# DDR4_SDRAM.net
KiCad netlist of a schematic drawn in Altium Designer
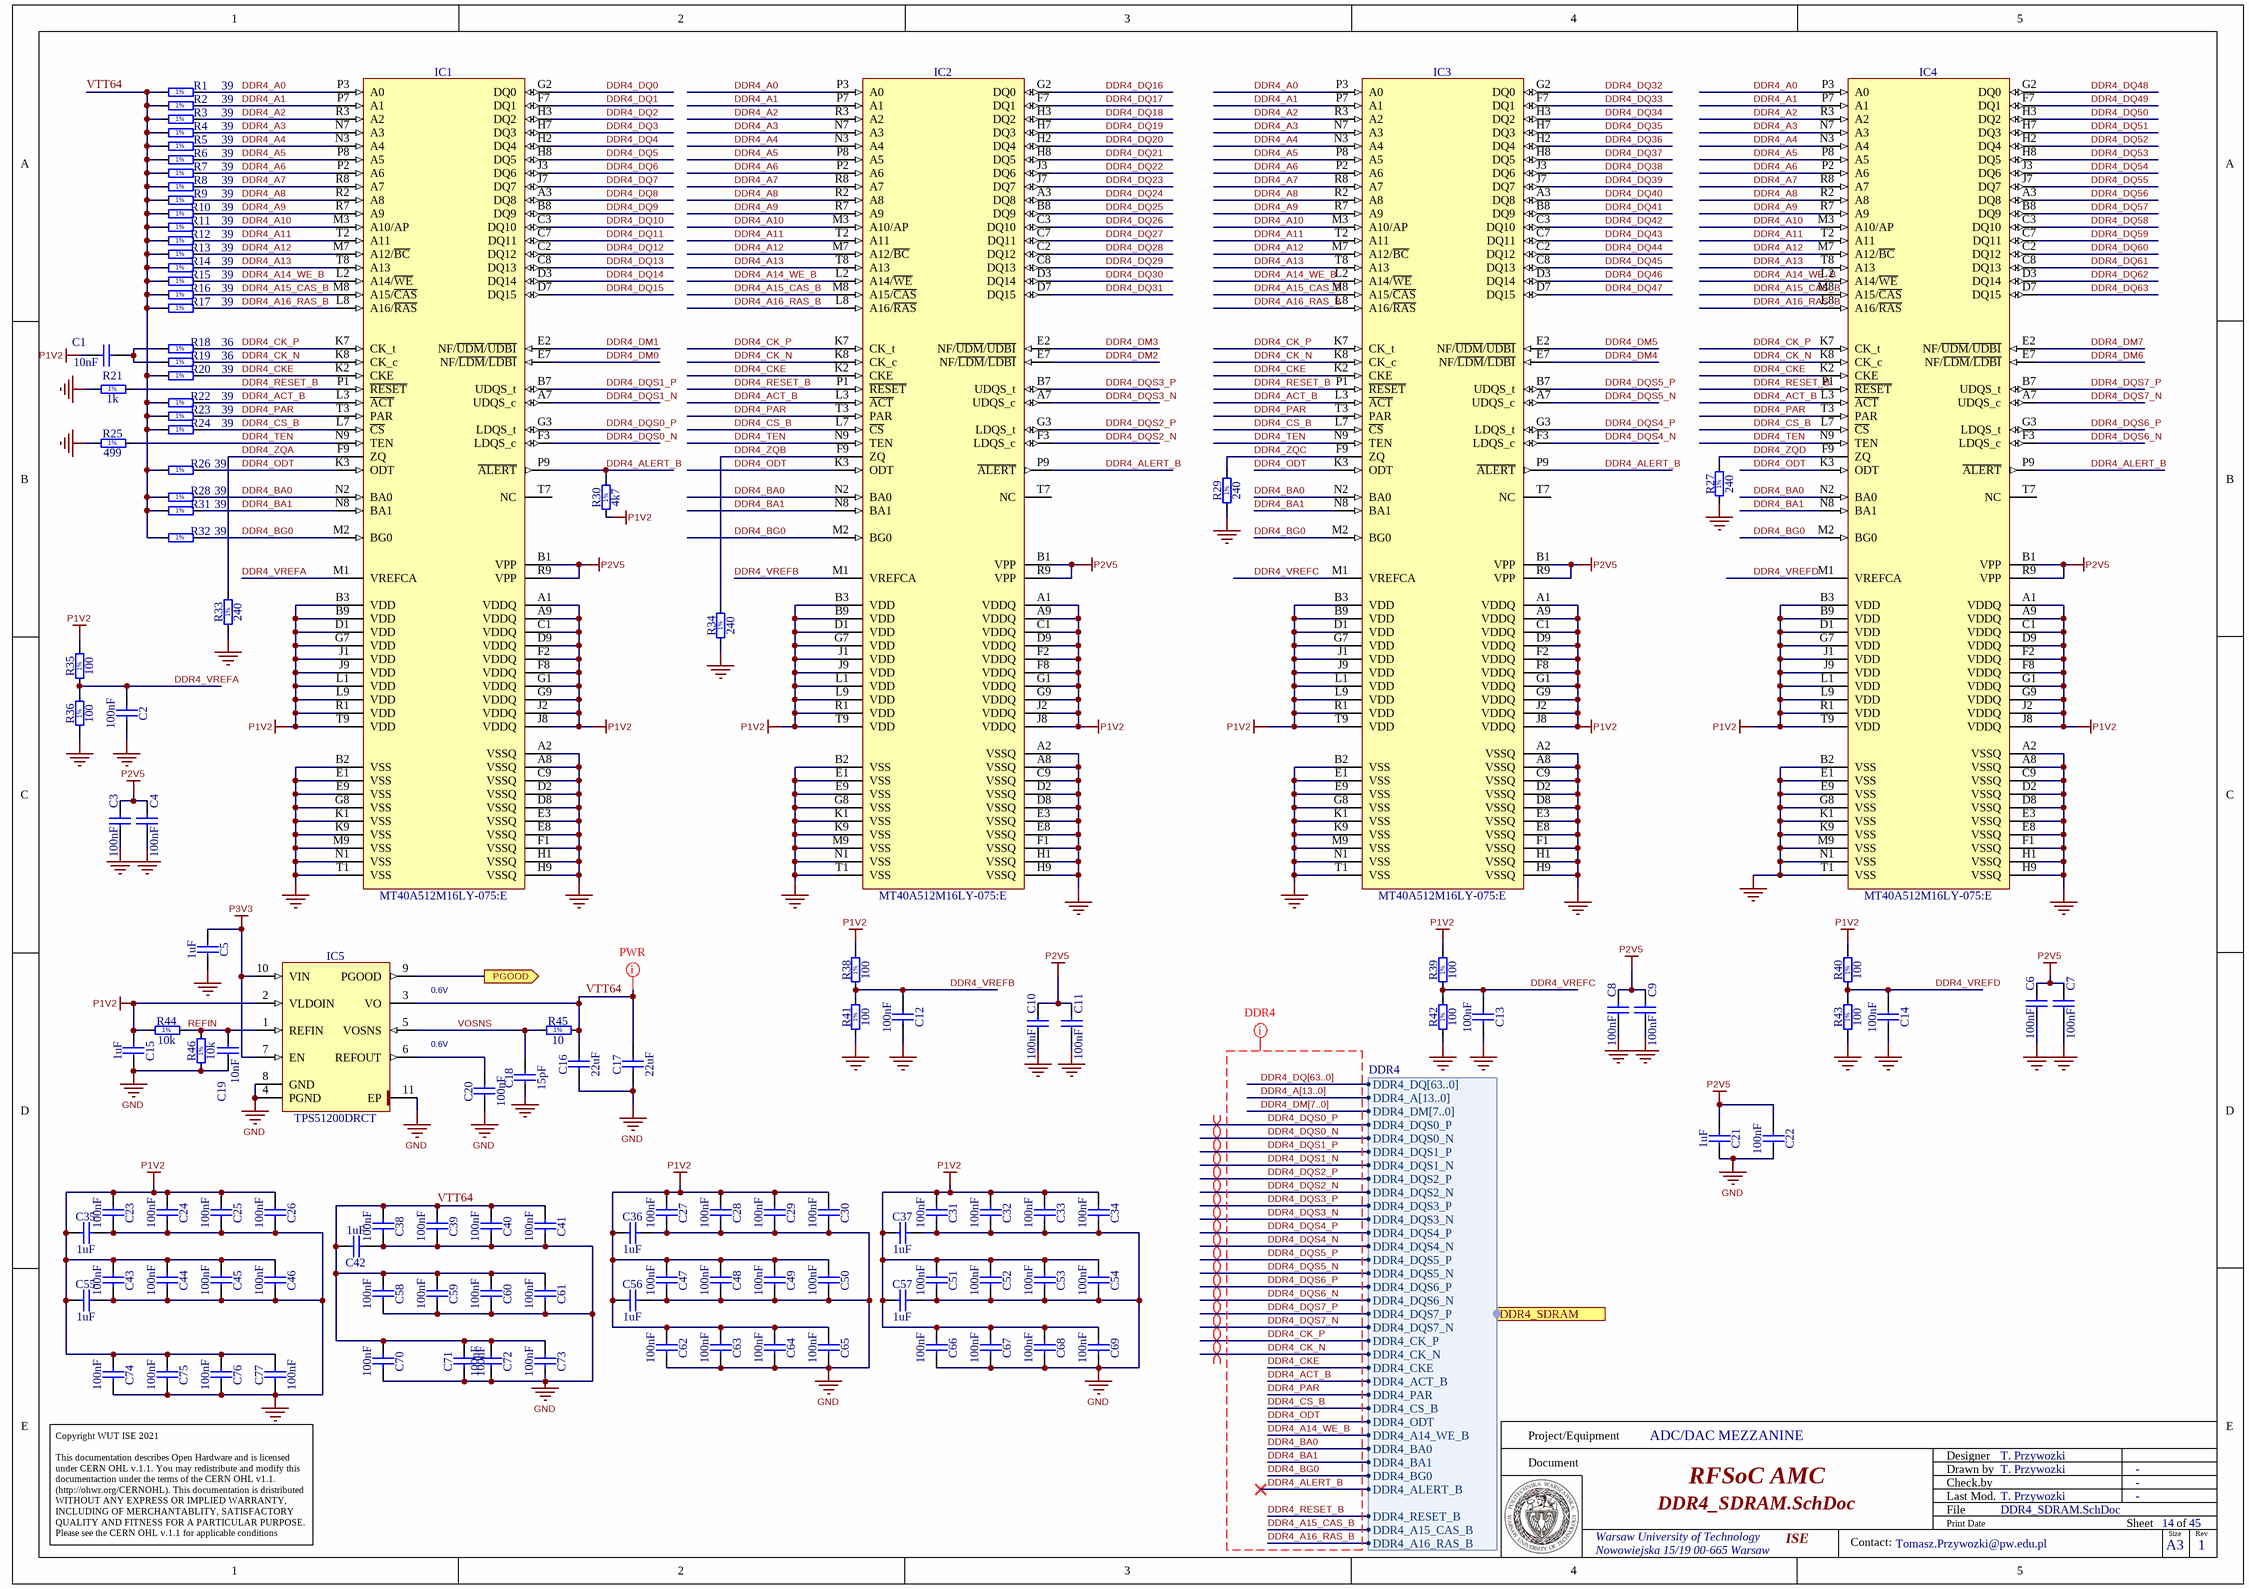
[diagram p0: DDR4_SDRAM.SchDoc]

(export (version "E")
  (design (tool "Eeschema 10.0.6"))
  (components
    (comp (ref "C1")
      (value "10nF")
      (footprint "CAPC0603X33N")
      (description "Non-polarised capacitor")
      (fields
        (field (name "PART NUMBER") "CC0201_10NF_10V_10%_X5R")
        (field (name "VOLTAGE") "10V")
        (field (name "AUTHOR") "CERN DEM JLC")
      )
      (libsource (lib "Capacitors") (part "Capacitor - non polarized"))
    )
    (comp (ref "C2")
      (value "100nF")
      (footprint "CAPC0603X33N")
      (description "Non-polarised capacitor")
      (fields
        (field (name "MANUFACTURER PART NUMBER") "CC0201_100NF_6.3V_10%_X5R")
        (field (name "MANUFACTURER") "GENERIC")
        (field (name "AUTHOR") "CERN DEM JLC")
      )
      (libsource (lib "Capacitors") (part "Capacitor - non polarized"))
    )
    (comp (ref "C3")
      (value "100nF")
      (footprint "CAPC0603X33N")
      (description "Non-polarised capacitor")
      (fields
        (field (name "MANUFACTURER PART NUMBER") "CC0201_100NF_6.3V_10%_X5R")
        (field (name "MANUFACTURER") "GENERIC")
        (field (name "AUTHOR") "CERN DEM JLC")
      )
      (libsource (lib "Capacitors") (part "Capacitor - non polarized"))
    )
    (comp (ref "C4")
      (value "100nF")
      (footprint "CAPC0603X33N")
      (description "Non-polarised capacitor")
      (fields
        (field (name "MANUFACTURER PART NUMBER") "CC0201_100NF_6.3V_10%_X5R")
        (field (name "MANUFACTURER") "GENERIC")
        (field (name "AUTHOR") "CERN DEM JLC")
      )
      (libsource (lib "Capacitors") (part "Capacitor - non polarized"))
    )
    (comp (ref "C5")
      (value "1uF")
      (footprint "CAPC1005X55N")
      (description "Non-polarised capacitor")
      (fields
        (field (name "MANUFACTURER PART NUMBER") "CC0402_1UF_16V_10%_X5R")
        (field (name "MANUFACTURER") "GENERIC")
        (field (name "AUTHOR") "CERN DEM JLC")
      )
      (libsource (lib "Capacitors") (part "Capacitor - non polarized"))
    )
    (comp (ref "C6")
      (value "100nF")
      (footprint "CAPC0603X33N")
      (description "Non-polarised capacitor")
      (fields
        (field (name "MANUFACTURER PART NUMBER") "CC0201_100NF_6.3V_10%_X5R")
        (field (name "MANUFACTURER") "GENERIC")
        (field (name "AUTHOR") "CERN DEM JLC")
      )
      (libsource (lib "Capacitors") (part "Capacitor - non polarized"))
    )
    (comp (ref "C7")
      (value "100nF")
      (footprint "CAPC0603X33N")
      (description "Non-polarised capacitor")
      (fields
        (field (name "MANUFACTURER PART NUMBER") "CC0201_100NF_6.3V_10%_X5R")
        (field (name "MANUFACTURER") "GENERIC")
        (field (name "AUTHOR") "CERN DEM JLC")
      )
      (libsource (lib "Capacitors") (part "Capacitor - non polarized"))
    )
    (comp (ref "C8")
      (value "100nF")
      (footprint "CAPC0603X33N")
      (description "Non-polarised capacitor")
      (fields
        (field (name "MANUFACTURER PART NUMBER") "CC0201_100NF_6.3V_10%_X5R")
        (field (name "MANUFACTURER") "GENERIC")
        (field (name "AUTHOR") "CERN DEM JLC")
      )
      (libsource (lib "Capacitors") (part "Capacitor - non polarized"))
    )
    (comp (ref "C9")
      (value "100nF")
      (footprint "CAPC0603X33N")
      (description "Non-polarised capacitor")
      (fields
        (field (name "MANUFACTURER PART NUMBER") "CC0201_100NF_6.3V_10%_X5R")
        (field (name "MANUFACTURER") "GENERIC")
        (field (name "AUTHOR") "CERN DEM JLC")
      )
      (libsource (lib "Capacitors") (part "Capacitor - non polarized"))
    )
    (comp (ref "C10")
      (value "100nF")
      (footprint "CAPC0603X33N")
      (description "Non-polarised capacitor")
      (fields
        (field (name "MANUFACTURER PART NUMBER") "CC0201_100NF_6.3V_10%_X5R")
        (field (name "MANUFACTURER") "GENERIC")
        (field (name "AUTHOR") "CERN DEM JLC")
      )
      (libsource (lib "Capacitors") (part "Capacitor - non polarized"))
    )
    (comp (ref "C11")
      (value "100nF")
      (footprint "CAPC0603X33N")
      (description "Non-polarised capacitor")
      (fields
        (field (name "MANUFACTURER PART NUMBER") "CC0201_100NF_6.3V_10%_X5R")
        (field (name "MANUFACTURER") "GENERIC")
        (field (name "AUTHOR") "CERN DEM JLC")
      )
      (libsource (lib "Capacitors") (part "Capacitor - non polarized"))
    )
    (comp (ref "C12")
      (value "100nF")
      (footprint "CAPC0603X33N")
      (description "Non-polarised capacitor")
      (fields
        (field (name "MANUFACTURER PART NUMBER") "CC0201_100NF_6.3V_10%_X5R")
        (field (name "MANUFACTURER") "GENERIC")
        (field (name "AUTHOR") "CERN DEM JLC")
      )
      (libsource (lib "Capacitors") (part "Capacitor - non polarized"))
    )
    (comp (ref "C13")
      (value "100nF")
      (footprint "CAPC0603X33N")
      (description "Non-polarised capacitor")
      (fields
        (field (name "MANUFACTURER PART NUMBER") "CC0201_100NF_6.3V_10%_X5R")
        (field (name "MANUFACTURER") "GENERIC")
        (field (name "AUTHOR") "CERN DEM JLC")
      )
      (libsource (lib "Capacitors") (part "Capacitor - non polarized"))
    )
    (comp (ref "C14")
      (value "100nF")
      (footprint "CAPC0603X33N")
      (description "Non-polarised capacitor")
      (fields
        (field (name "MANUFACTURER PART NUMBER") "CC0201_100NF_6.3V_10%_X5R")
        (field (name "MANUFACTURER") "GENERIC")
        (field (name "AUTHOR") "CERN DEM JLC")
      )
      (libsource (lib "Capacitors") (part "Capacitor - non polarized"))
    )
    (comp (ref "C15")
      (value "1uF")
      (footprint "CAPC1005X55N")
      (description "Non-polarised capacitor")
      (fields
        (field (name "MANUFACTURER PART NUMBER") "CC0402_1UF_16V_10%_X5R")
        (field (name "MANUFACTURER") "GENERIC")
        (field (name "AUTHOR") "CERN DEM JLC")
      )
      (libsource (lib "Capacitors") (part "Capacitor - non polarized"))
    )
    (comp (ref "C16")
      (value "22uF")
      (footprint "CAPC2012X135N")
      (description "Non-polarised capacitor")
      (fields
        (field (name "MANUFACTURER PART NUMBER") "CC0805_22UF_10V_+80%-20%_Y5V")
        (field (name "MANUFACTURER") "GENERIC")
        (field (name "AUTHOR") "CERN DEM JLC")
      )
      (libsource (lib "Capacitors") (part "Capacitor - non polarized"))
    )
    (comp (ref "C17")
      (value "22uF")
      (footprint "CAPC2012X135N")
      (description "Non-polarised capacitor")
      (fields
        (field (name "MANUFACTURER PART NUMBER") "CC0805_22UF_10V_+80%-20%_Y5V")
        (field (name "MANUFACTURER") "GENERIC")
        (field (name "AUTHOR") "CERN DEM JLC")
      )
      (libsource (lib "Capacitors") (part "Capacitor - non polarized"))
    )
    (comp (ref "C18")
      (value "15pF")
      (footprint "CAPC1005X55N")
      (description "Non-polarised capacitor")
      (fields
        (field (name "MANUFACTURER PART NUMBER") "CC0402_15PF_50V_5%_C0G")
        (field (name "MANUFACTURER") "GENERIC")
        (field (name "AUTHOR") "CERN DEM JLC")
      )
      (libsource (lib "Capacitors") (part "Capacitor - non polarized"))
    )
    (comp (ref "C19")
      (value "10nF")
      (footprint "CAPC1005X55N")
      (description "Non-polarised capacitor")
      (fields
        (field (name "MANUFACTURER PART NUMBER") "CC0402_10NF_25V_10%_X7R")
        (field (name "MANUFACTURER") "GENERIC")
        (field (name "AUTHOR") "CERN DEM JLC")
      )
      (libsource (lib "Capacitors") (part "Capacitor - non polarized"))
    )
    (comp (ref "C20")
      (value "100nF")
      (footprint "CAPC0603X33N")
      (description "Non-polarised capacitor")
      (fields
        (field (name "MANUFACTURER PART NUMBER") "CC0201_100NF_6.3V_10%_X5R")
        (field (name "MANUFACTURER") "GENERIC")
        (field (name "AUTHOR") "CERN DEM JLC")
      )
      (libsource (lib "Capacitors") (part "Capacitor - non polarized"))
    )
    (comp (ref "C21")
      (value "1uF")
      (footprint "CAPC1005X55N")
      (description "Non-polarised capacitor")
      (fields
        (field (name "MANUFACTURER PART NUMBER") "CC0402_1UF_16V_10%_X5R")
        (field (name "MANUFACTURER") "GENERIC")
        (field (name "AUTHOR") "CERN DEM JLC")
      )
      (libsource (lib "Capacitors") (part "Capacitor - non polarized"))
    )
    (comp (ref "C22")
      (value "100nF")
      (footprint "CAPC0603X33N")
      (description "Non-polarised capacitor")
      (fields
        (field (name "MANUFACTURER PART NUMBER") "CC0201_100NF_6.3V_10%_X5R")
        (field (name "MANUFACTURER") "GENERIC")
        (field (name "AUTHOR") "CERN DEM JLC")
      )
      (libsource (lib "Capacitors") (part "Capacitor - non polarized"))
    )
    (comp (ref "C23")
      (value "100nF")
      (footprint "CAPC0603X33N")
      (description "Non-polarised capacitor")
      (fields
        (field (name "MANUFACTURER PART NUMBER") "CC0201_100NF_6.3V_10%_X5R")
        (field (name "MANUFACTURER") "GENERIC")
        (field (name "AUTHOR") "CERN DEM JLC")
      )
      (libsource (lib "Capacitors") (part "Capacitor - non polarized"))
    )
    (comp (ref "C24")
      (value "100nF")
      (footprint "CAPC0603X33N")
      (description "Non-polarised capacitor")
      (fields
        (field (name "MANUFACTURER PART NUMBER") "CC0201_100NF_6.3V_10%_X5R")
        (field (name "MANUFACTURER") "GENERIC")
        (field (name "AUTHOR") "CERN DEM JLC")
      )
      (libsource (lib "Capacitors") (part "Capacitor - non polarized"))
    )
    (comp (ref "C25")
      (value "100nF")
      (footprint "CAPC0603X33N")
      (description "Non-polarised capacitor")
      (fields
        (field (name "MANUFACTURER PART NUMBER") "CC0201_100NF_6.3V_10%_X5R")
        (field (name "MANUFACTURER") "GENERIC")
        (field (name "AUTHOR") "CERN DEM JLC")
      )
      (libsource (lib "Capacitors") (part "Capacitor - non polarized"))
    )
    (comp (ref "C26")
      (value "100nF")
      (footprint "CAPC0603X33N")
      (description "Non-polarised capacitor")
      (fields
        (field (name "MANUFACTURER PART NUMBER") "CC0201_100NF_6.3V_10%_X5R")
        (field (name "MANUFACTURER") "GENERIC")
        (field (name "AUTHOR") "CERN DEM JLC")
      )
      (libsource (lib "Capacitors") (part "Capacitor - non polarized"))
    )
    (comp (ref "C27")
      (value "100nF")
      (footprint "CAPC0603X33N")
      (description "Non-polarised capacitor")
      (fields
        (field (name "MANUFACTURER PART NUMBER") "CC0201_100NF_6.3V_10%_X5R")
        (field (name "MANUFACTURER") "GENERIC")
        (field (name "AUTHOR") "CERN DEM JLC")
      )
      (libsource (lib "Capacitors") (part "Capacitor - non polarized"))
    )
    (comp (ref "C28")
      (value "100nF")
      (footprint "CAPC0603X33N")
      (description "Non-polarised capacitor")
      (fields
        (field (name "MANUFACTURER PART NUMBER") "CC0201_100NF_6.3V_10%_X5R")
        (field (name "MANUFACTURER") "GENERIC")
        (field (name "AUTHOR") "CERN DEM JLC")
      )
      (libsource (lib "Capacitors") (part "Capacitor - non polarized"))
    )
    (comp (ref "C29")
      (value "100nF")
      (footprint "CAPC0603X33N")
      (description "Non-polarised capacitor")
      (fields
        (field (name "MANUFACTURER PART NUMBER") "CC0201_100NF_6.3V_10%_X5R")
        (field (name "MANUFACTURER") "GENERIC")
        (field (name "AUTHOR") "CERN DEM JLC")
      )
      (libsource (lib "Capacitors") (part "Capacitor - non polarized"))
    )
    (comp (ref "C30")
      (value "100nF")
      (footprint "CAPC0603X33N")
      (description "Non-polarised capacitor")
      (fields
        (field (name "MANUFACTURER PART NUMBER") "CC0201_100NF_6.3V_10%_X5R")
        (field (name "MANUFACTURER") "GENERIC")
        (field (name "AUTHOR") "CERN DEM JLC")
      )
      (libsource (lib "Capacitors") (part "Capacitor - non polarized"))
    )
    (comp (ref "C31")
      (value "100nF")
      (footprint "CAPC0603X33N")
      (description "Non-polarised capacitor")
      (fields
        (field (name "MANUFACTURER PART NUMBER") "CC0201_100NF_6.3V_10%_X5R")
        (field (name "MANUFACTURER") "GENERIC")
        (field (name "AUTHOR") "CERN DEM JLC")
      )
      (libsource (lib "Capacitors") (part "Capacitor - non polarized"))
    )
    (comp (ref "C32")
      (value "100nF")
      (footprint "CAPC0603X33N")
      (description "Non-polarised capacitor")
      (fields
        (field (name "MANUFACTURER PART NUMBER") "CC0201_100NF_6.3V_10%_X5R")
        (field (name "MANUFACTURER") "GENERIC")
        (field (name "AUTHOR") "CERN DEM JLC")
      )
      (libsource (lib "Capacitors") (part "Capacitor - non polarized"))
    )
    (comp (ref "C33")
      (value "100nF")
      (footprint "CAPC0603X33N")
      (description "Non-polarised capacitor")
      (fields
        (field (name "MANUFACTURER PART NUMBER") "CC0201_100NF_6.3V_10%_X5R")
        (field (name "MANUFACTURER") "GENERIC")
        (field (name "AUTHOR") "CERN DEM JLC")
      )
      (libsource (lib "Capacitors") (part "Capacitor - non polarized"))
    )
    (comp (ref "C34")
      (value "100nF")
      (footprint "CAPC0603X33N")
      (description "Non-polarised capacitor")
      (fields
        (field (name "MANUFACTURER PART NUMBER") "CC0201_100NF_6.3V_10%_X5R")
        (field (name "MANUFACTURER") "GENERIC")
        (field (name "AUTHOR") "CERN DEM JLC")
      )
      (libsource (lib "Capacitors") (part "Capacitor - non polarized"))
    )
    (comp (ref "C35")
      (value "1uF")
      (footprint "CAPC1005X55N")
      (description "Non-polarised capacitor")
      (fields
        (field (name "MANUFACTURER PART NUMBER") "CC0402_1UF_16V_10%_X5R")
        (field (name "MANUFACTURER") "GENERIC")
        (field (name "AUTHOR") "CERN DEM JLC")
      )
      (libsource (lib "Capacitors") (part "Capacitor - non polarized"))
    )
    (comp (ref "C36")
      (value "1uF")
      (footprint "CAPC1005X55N")
      (description "Non-polarised capacitor")
      (fields
        (field (name "MANUFACTURER PART NUMBER") "CC0402_1UF_16V_10%_X5R")
        (field (name "MANUFACTURER") "GENERIC")
        (field (name "AUTHOR") "CERN DEM JLC")
      )
      (libsource (lib "Capacitors") (part "Capacitor - non polarized"))
    )
    (comp (ref "C37")
      (value "1uF")
      (footprint "CAPC1005X55N")
      (description "Non-polarised capacitor")
      (fields
        (field (name "MANUFACTURER PART NUMBER") "CC0402_1UF_16V_10%_X5R")
        (field (name "MANUFACTURER") "GENERIC")
        (field (name "AUTHOR") "CERN DEM JLC")
      )
      (libsource (lib "Capacitors") (part "Capacitor - non polarized"))
    )
    (comp (ref "C38")
      (value "100nF")
      (footprint "CAPC0603X33N")
      (description "Non-polarised capacitor")
      (fields
        (field (name "MANUFACTURER PART NUMBER") "CC0201_100NF_6.3V_10%_X5R")
        (field (name "MANUFACTURER") "GENERIC")
        (field (name "AUTHOR") "CERN DEM JLC")
      )
      (libsource (lib "Capacitors") (part "Capacitor - non polarized"))
    )
    (comp (ref "C39")
      (value "100nF")
      (footprint "CAPC0603X33N")
      (description "Non-polarised capacitor")
      (fields
        (field (name "MANUFACTURER PART NUMBER") "CC0201_100NF_6.3V_10%_X5R")
        (field (name "MANUFACTURER") "GENERIC")
        (field (name "AUTHOR") "CERN DEM JLC")
      )
      (libsource (lib "Capacitors") (part "Capacitor - non polarized"))
    )
    (comp (ref "C40")
      (value "100nF")
      (footprint "CAPC0603X33N")
      (description "Non-polarised capacitor")
      (fields
        (field (name "MANUFACTURER PART NUMBER") "CC0201_100NF_6.3V_10%_X5R")
        (field (name "MANUFACTURER") "GENERIC")
        (field (name "AUTHOR") "CERN DEM JLC")
      )
      (libsource (lib "Capacitors") (part "Capacitor - non polarized"))
    )
    (comp (ref "C41")
      (value "100nF")
      (footprint "CAPC0603X33N")
      (description "Non-polarised capacitor")
      (fields
        (field (name "MANUFACTURER PART NUMBER") "CC0201_100NF_6.3V_10%_X5R")
        (field (name "MANUFACTURER") "GENERIC")
        (field (name "AUTHOR") "CERN DEM JLC")
      )
      (libsource (lib "Capacitors") (part "Capacitor - non polarized"))
    )
    (comp (ref "C42")
      (value "1uF")
      (footprint "CAPC1005X55N")
      (description "Non-polarised capacitor")
      (fields
        (field (name "MANUFACTURER PART NUMBER") "CC0402_1UF_16V_10%_X5R")
        (field (name "MANUFACTURER") "GENERIC")
        (field (name "AUTHOR") "CERN DEM JLC")
      )
      (libsource (lib "Capacitors") (part "Capacitor - non polarized"))
    )
    (comp (ref "C43")
      (value "100nF")
      (footprint "CAPC0603X33N")
      (description "Non-polarised capacitor")
      (fields
        (field (name "MANUFACTURER PART NUMBER") "CC0201_100NF_6.3V_10%_X5R")
        (field (name "MANUFACTURER") "GENERIC")
        (field (name "AUTHOR") "CERN DEM JLC")
      )
      (libsource (lib "Capacitors") (part "Capacitor - non polarized"))
    )
    (comp (ref "C44")
      (value "100nF")
      (footprint "CAPC0603X33N")
      (description "Non-polarised capacitor")
      (fields
        (field (name "MANUFACTURER PART NUMBER") "CC0201_100NF_6.3V_10%_X5R")
        (field (name "MANUFACTURER") "GENERIC")
        (field (name "AUTHOR") "CERN DEM JLC")
      )
      (libsource (lib "Capacitors") (part "Capacitor - non polarized"))
    )
    (comp (ref "C45")
      (value "100nF")
      (footprint "CAPC0603X33N")
      (description "Non-polarised capacitor")
      (fields
        (field (name "MANUFACTURER PART NUMBER") "CC0201_100NF_6.3V_10%_X5R")
        (field (name "MANUFACTURER") "GENERIC")
        (field (name "AUTHOR") "CERN DEM JLC")
      )
      (libsource (lib "Capacitors") (part "Capacitor - non polarized"))
    )
    (comp (ref "C46")
      (value "100nF")
      (footprint "CAPC0603X33N")
      (description "Non-polarised capacitor")
      (fields
        (field (name "MANUFACTURER PART NUMBER") "CC0201_100NF_6.3V_10%_X5R")
        (field (name "MANUFACTURER") "GENERIC")
        (field (name "AUTHOR") "CERN DEM JLC")
      )
      (libsource (lib "Capacitors") (part "Capacitor - non polarized"))
    )
    (comp (ref "C47")
      (value "100nF")
      (footprint "CAPC0603X33N")
      (description "Non-polarised capacitor")
      (fields
        (field (name "MANUFACTURER PART NUMBER") "CC0201_100NF_6.3V_10%_X5R")
        (field (name "MANUFACTURER") "GENERIC")
        (field (name "AUTHOR") "CERN DEM JLC")
      )
      (libsource (lib "Capacitors") (part "Capacitor - non polarized"))
    )
    (comp (ref "C48")
      (value "100nF")
      (footprint "CAPC0603X33N")
      (description "Non-polarised capacitor")
      (fields
        (field (name "MANUFACTURER PART NUMBER") "CC0201_100NF_6.3V_10%_X5R")
        (field (name "MANUFACTURER") "GENERIC")
        (field (name "AUTHOR") "CERN DEM JLC")
      )
      (libsource (lib "Capacitors") (part "Capacitor - non polarized"))
    )
    (comp (ref "C49")
      (value "100nF")
      (footprint "CAPC0603X33N")
      (description "Non-polarised capacitor")
      (fields
        (field (name "MANUFACTURER PART NUMBER") "CC0201_100NF_6.3V_10%_X5R")
        (field (name "MANUFACTURER") "GENERIC")
        (field (name "AUTHOR") "CERN DEM JLC")
      )
      (libsource (lib "Capacitors") (part "Capacitor - non polarized"))
    )
    (comp (ref "C50")
      (value "100nF")
      (footprint "CAPC0603X33N")
      (description "Non-polarised capacitor")
      (fields
        (field (name "MANUFACTURER PART NUMBER") "CC0201_100NF_6.3V_10%_X5R")
        (field (name "MANUFACTURER") "GENERIC")
        (field (name "AUTHOR") "CERN DEM JLC")
      )
      (libsource (lib "Capacitors") (part "Capacitor - non polarized"))
    )
    (comp (ref "C51")
      (value "100nF")
      (footprint "CAPC0603X33N")
      (description "Non-polarised capacitor")
      (fields
        (field (name "MANUFACTURER PART NUMBER") "CC0201_100NF_6.3V_10%_X5R")
        (field (name "MANUFACTURER") "GENERIC")
        (field (name "AUTHOR") "CERN DEM JLC")
      )
      (libsource (lib "Capacitors") (part "Capacitor - non polarized"))
    )
    (comp (ref "C52")
      (value "100nF")
      (footprint "CAPC0603X33N")
      (description "Non-polarised capacitor")
      (fields
        (field (name "MANUFACTURER PART NUMBER") "CC0201_100NF_6.3V_10%_X5R")
        (field (name "MANUFACTURER") "GENERIC")
        (field (name "AUTHOR") "CERN DEM JLC")
      )
      (libsource (lib "Capacitors") (part "Capacitor - non polarized"))
    )
    (comp (ref "C53")
      (value "100nF")
      (footprint "CAPC0603X33N")
      (description "Non-polarised capacitor")
      (fields
        (field (name "MANUFACTURER PART NUMBER") "CC0201_100NF_6.3V_10%_X5R")
        (field (name "MANUFACTURER") "GENERIC")
        (field (name "AUTHOR") "CERN DEM JLC")
      )
      (libsource (lib "Capacitors") (part "Capacitor - non polarized"))
    )
    (comp (ref "C54")
      (value "100nF")
      (footprint "CAPC0603X33N")
      (description "Non-polarised capacitor")
      (fields
        (field (name "MANUFACTURER PART NUMBER") "CC0201_100NF_6.3V_10%_X5R")
        (field (name "MANUFACTURER") "GENERIC")
        (field (name "AUTHOR") "CERN DEM JLC")
      )
      (libsource (lib "Capacitors") (part "Capacitor - non polarized"))
    )
    (comp (ref "C55")
      (value "1uF")
      (footprint "CAPC1005X55N")
      (description "Non-polarised capacitor")
      (fields
        (field (name "MANUFACTURER PART NUMBER") "CC0402_1UF_16V_10%_X5R")
        (field (name "MANUFACTURER") "GENERIC")
        (field (name "AUTHOR") "CERN DEM JLC")
      )
      (libsource (lib "Capacitors") (part "Capacitor - non polarized"))
    )
    (comp (ref "C56")
      (value "1uF")
      (footprint "CAPC1005X55N")
      (description "Non-polarised capacitor")
      (fields
        (field (name "MANUFACTURER PART NUMBER") "CC0402_1UF_16V_10%_X5R")
        (field (name "MANUFACTURER") "GENERIC")
        (field (name "AUTHOR") "CERN DEM JLC")
      )
      (libsource (lib "Capacitors") (part "Capacitor - non polarized"))
    )
    (comp (ref "C57")
      (value "1uF")
      (footprint "CAPC1005X55N")
      (description "Non-polarised capacitor")
      (fields
        (field (name "MANUFACTURER PART NUMBER") "CC0402_1UF_16V_10%_X5R")
        (field (name "MANUFACTURER") "GENERIC")
        (field (name "AUTHOR") "CERN DEM JLC")
      )
      (libsource (lib "Capacitors") (part "Capacitor - non polarized"))
    )
    (comp (ref "C58")
      (value "100nF")
      (footprint "CAPC0603X33N")
      (description "Non-polarised capacitor")
      (fields
        (field (name "MANUFACTURER PART NUMBER") "CC0201_100NF_6.3V_10%_X5R")
        (field (name "MANUFACTURER") "GENERIC")
        (field (name "AUTHOR") "CERN DEM JLC")
      )
      (libsource (lib "Capacitors") (part "Capacitor - non polarized"))
    )
    (comp (ref "C59")
      (value "100nF")
      (footprint "CAPC0603X33N")
      (description "Non-polarised capacitor")
      (fields
        (field (name "MANUFACTURER PART NUMBER") "CC0201_100NF_6.3V_10%_X5R")
        (field (name "MANUFACTURER") "GENERIC")
        (field (name "AUTHOR") "CERN DEM JLC")
      )
      (libsource (lib "Capacitors") (part "Capacitor - non polarized"))
    )
    (comp (ref "C60")
      (value "100nF")
      (footprint "CAPC0603X33N")
      (description "Non-polarised capacitor")
      (fields
        (field (name "MANUFACTURER PART NUMBER") "CC0201_100NF_6.3V_10%_X5R")
        (field (name "MANUFACTURER") "GENERIC")
        (field (name "AUTHOR") "CERN DEM JLC")
      )
      (libsource (lib "Capacitors") (part "Capacitor - non polarized"))
    )
    (comp (ref "C61")
      (value "100nF")
      (footprint "CAPC0603X33N")
      (description "Non-polarised capacitor")
      (fields
        (field (name "MANUFACTURER PART NUMBER") "CC0201_100NF_6.3V_10%_X5R")
        (field (name "MANUFACTURER") "GENERIC")
        (field (name "AUTHOR") "CERN DEM JLC")
      )
      (libsource (lib "Capacitors") (part "Capacitor - non polarized"))
    )
    (comp (ref "C62")
      (value "100nF")
      (footprint "CAPC0603X33N")
      (description "Non-polarised capacitor")
      (fields
        (field (name "MANUFACTURER PART NUMBER") "CC0201_100NF_6.3V_10%_X5R")
        (field (name "MANUFACTURER") "GENERIC")
        (field (name "AUTHOR") "CERN DEM JLC")
      )
      (libsource (lib "Capacitors") (part "Capacitor - non polarized"))
    )
    (comp (ref "C63")
      (value "100nF")
      (footprint "CAPC0603X33N")
      (description "Non-polarised capacitor")
      (fields
        (field (name "MANUFACTURER PART NUMBER") "CC0201_100NF_6.3V_10%_X5R")
        (field (name "MANUFACTURER") "GENERIC")
        (field (name "AUTHOR") "CERN DEM JLC")
      )
      (libsource (lib "Capacitors") (part "Capacitor - non polarized"))
    )
    (comp (ref "C64")
      (value "100nF")
      (footprint "CAPC0603X33N")
      (description "Non-polarised capacitor")
      (fields
        (field (name "MANUFACTURER PART NUMBER") "CC0201_100NF_6.3V_10%_X5R")
        (field (name "MANUFACTURER") "GENERIC")
        (field (name "AUTHOR") "CERN DEM JLC")
      )
      (libsource (lib "Capacitors") (part "Capacitor - non polarized"))
    )
    (comp (ref "C65")
      (value "100nF")
      (footprint "CAPC0603X33N")
      (description "Non-polarised capacitor")
      (fields
        (field (name "MANUFACTURER PART NUMBER") "CC0201_100NF_6.3V_10%_X5R")
        (field (name "MANUFACTURER") "GENERIC")
        (field (name "AUTHOR") "CERN DEM JLC")
      )
      (libsource (lib "Capacitors") (part "Capacitor - non polarized"))
    )
    (comp (ref "C66")
      (value "100nF")
      (footprint "CAPC0603X33N")
      (description "Non-polarised capacitor")
      (fields
        (field (name "MANUFACTURER PART NUMBER") "CC0201_100NF_6.3V_10%_X5R")
        (field (name "MANUFACTURER") "GENERIC")
        (field (name "AUTHOR") "CERN DEM JLC")
      )
      (libsource (lib "Capacitors") (part "Capacitor - non polarized"))
    )
    (comp (ref "C67")
      (value "100nF")
      (footprint "CAPC0603X33N")
      (description "Non-polarised capacitor")
      (fields
        (field (name "MANUFACTURER PART NUMBER") "CC0201_100NF_6.3V_10%_X5R")
        (field (name "MANUFACTURER") "GENERIC")
        (field (name "AUTHOR") "CERN DEM JLC")
      )
      (libsource (lib "Capacitors") (part "Capacitor - non polarized"))
    )
    (comp (ref "C68")
      (value "100nF")
      (footprint "CAPC0603X33N")
      (description "Non-polarised capacitor")
      (fields
        (field (name "MANUFACTURER PART NUMBER") "CC0201_100NF_6.3V_10%_X5R")
        (field (name "MANUFACTURER") "GENERIC")
        (field (name "AUTHOR") "CERN DEM JLC")
      )
      (libsource (lib "Capacitors") (part "Capacitor - non polarized"))
    )
    (comp (ref "C69")
      (value "100nF")
      (footprint "CAPC0603X33N")
      (description "Non-polarised capacitor")
      (fields
        (field (name "MANUFACTURER PART NUMBER") "CC0201_100NF_6.3V_10%_X5R")
        (field (name "MANUFACTURER") "GENERIC")
        (field (name "AUTHOR") "CERN DEM JLC")
      )
      (libsource (lib "Capacitors") (part "Capacitor - non polarized"))
    )
    (comp (ref "C70")
      (value "100nF")
      (footprint "CAPC0603X33N")
      (description "Non-polarised capacitor")
      (fields
        (field (name "MANUFACTURER PART NUMBER") "CC0201_100NF_6.3V_10%_X5R")
        (field (name "MANUFACTURER") "GENERIC")
        (field (name "AUTHOR") "CERN DEM JLC")
      )
      (libsource (lib "Capacitors") (part "Capacitor - non polarized"))
    )
    (comp (ref "C71")
      (value "100nF")
      (footprint "CAPC0603X33N")
      (description "Non-polarised capacitor")
      (fields
        (field (name "MANUFACTURER PART NUMBER") "CC0201_100NF_6.3V_10%_X5R")
        (field (name "MANUFACTURER") "GENERIC")
        (field (name "AUTHOR") "CERN DEM JLC")
      )
      (libsource (lib "Capacitors") (part "Capacitor - non polarized"))
    )
    (comp (ref "C72")
      (value "100nF")
      (footprint "CAPC0603X33N")
      (description "Non-polarised capacitor")
      (fields
        (field (name "MANUFACTURER PART NUMBER") "CC0201_100NF_6.3V_10%_X5R")
        (field (name "MANUFACTURER") "GENERIC")
        (field (name "AUTHOR") "CERN DEM JLC")
      )
      (libsource (lib "Capacitors") (part "Capacitor - non polarized"))
    )
    (comp (ref "C73")
      (value "100nF")
      (footprint "CAPC0603X33N")
      (description "Non-polarised capacitor")
      (fields
        (field (name "MANUFACTURER PART NUMBER") "CC0201_100NF_6.3V_10%_X5R")
        (field (name "MANUFACTURER") "GENERIC")
        (field (name "AUTHOR") "CERN DEM JLC")
      )
      (libsource (lib "Capacitors") (part "Capacitor - non polarized"))
    )
    (comp (ref "C74")
      (value "100nF")
      (footprint "CAPC0603X33N")
      (description "Non-polarised capacitor")
      (fields
        (field (name "MANUFACTURER PART NUMBER") "CC0201_100NF_6.3V_10%_X5R")
        (field (name "MANUFACTURER") "GENERIC")
        (field (name "AUTHOR") "CERN DEM JLC")
      )
      (libsource (lib "Capacitors") (part "Capacitor - non polarized"))
    )
    (comp (ref "C75")
      (value "100nF")
      (footprint "CAPC0603X33N")
      (description "Non-polarised capacitor")
      (fields
        (field (name "MANUFACTURER PART NUMBER") "CC0201_100NF_6.3V_10%_X5R")
        (field (name "MANUFACTURER") "GENERIC")
        (field (name "AUTHOR") "CERN DEM JLC")
      )
      (libsource (lib "Capacitors") (part "Capacitor - non polarized"))
    )
    (comp (ref "C76")
      (value "100nF")
      (footprint "CAPC0603X33N")
      (description "Non-polarised capacitor")
      (fields
        (field (name "MANUFACTURER PART NUMBER") "CC0201_100NF_6.3V_10%_X5R")
        (field (name "MANUFACTURER") "GENERIC")
        (field (name "AUTHOR") "CERN DEM JLC")
      )
      (libsource (lib "Capacitors") (part "Capacitor - non polarized"))
    )
    (comp (ref "C77")
      (value "100nF")
      (footprint "CAPC0603X33N")
      (description "Non-polarised capacitor")
      (fields
        (field (name "MANUFACTURER PART NUMBER") "CC0201_100NF_6.3V_10%_X5R")
        (field (name "MANUFACTURER") "GENERIC")
        (field (name "AUTHOR") "CERN DEM JLC")
      )
      (libsource (lib "Capacitors") (part "Capacitor - non polarized"))
    )
    (comp (ref "IC1")
      (value "MT40A512M16LY-075:E")
      (footprint "BGA96C80P9X16_750X1350X120")
      (description "+1.2V, 8Gb (512 Meg x 16 x 8 Banks) DDR4 SDRAM")
      (fields (field (name "MANUFACTURER") "MICRON TECHNOLOGY") (field (name "AUTHOR") "CERN DEM WB"))
      (libsource (lib "ICs And Semiconductors") (part "MT40A512M16LY"))
    )
    (comp (ref "IC2")
      (value "MT40A512M16LY-075:E")
      (footprint "BGA96C80P9X16_750X1350X120")
      (description "+1.2V, 8Gb (512 Meg x 16 x 8 Banks) DDR4 SDRAM")
      (fields (field (name "MANUFACTURER") "MICRON TECHNOLOGY") (field (name "AUTHOR") "CERN DEM WB"))
      (libsource (lib "ICs And Semiconductors") (part "MT40A512M16LY"))
    )
    (comp (ref "IC3")
      (value "MT40A512M16LY-075:E")
      (footprint "BGA96C80P9X16_750X1350X120")
      (description "+1.2V, 8Gb (512 Meg x 16 x 8 Banks) DDR4 SDRAM")
      (fields (field (name "MANUFACTURER") "MICRON TECHNOLOGY") (field (name "AUTHOR") "CERN DEM WB"))
      (libsource (lib "ICs And Semiconductors") (part "MT40A512M16LY"))
    )
    (comp (ref "IC4")
      (value "MT40A512M16LY-075:E")
      (footprint "BGA96C80P9X16_750X1350X120")
      (description "+1.2V, 8Gb (512 Meg x 16 x 8 Banks) DDR4 SDRAM")
      (fields (field (name "MANUFACTURER") "MICRON TECHNOLOGY") (field (name "AUTHOR") "CERN DEM WB"))
      (libsource (lib "ICs And Semiconductors") (part "MT40A512M16LY"))
    )
    (comp (ref "IC5")
      (value "TPS51200DRCT")
      (footprint "TEXAS_DRC (S-PVSON-N10)")
      (description "Sink/Source DDR Termination Regulator")
      (fields (field (name "MANUFACTURER") "TEXAS INSTRUMENTS") (field (name "AUTHOR") "CERN DEM JLC"))
      (libsource (lib "ICs And Semiconductors") (part "TPS51200DRC"))
    )
    (comp (ref "R1")
      (value "39")
      (footprint "RESC1005X40N")
      (description "Resistor - 1%")
      (fields
        (field (name "MANUFACTURER PART NUMBER") "R0402_39R_1%_0.0625W_100PPM")
        (field (name "MANUFACTURER") "GENERIC")
        (field (name "AUTHOR") "CERN DEM JLC")
      )
      (libsource (lib "Resistors") (part "Resistor - 1%"))
    )
    (comp (ref "R2")
      (value "39")
      (footprint "RESC1005X40N")
      (description "Resistor - 1%")
      (fields
        (field (name "MANUFACTURER PART NUMBER") "R0402_39R_1%_0.0625W_100PPM")
        (field (name "MANUFACTURER") "GENERIC")
        (field (name "AUTHOR") "CERN DEM JLC")
      )
      (libsource (lib "Resistors") (part "Resistor - 1%"))
    )
    (comp (ref "R3")
      (value "39")
      (footprint "RESC1005X40N")
      (description "Resistor - 1%")
      (fields
        (field (name "MANUFACTURER PART NUMBER") "R0402_39R_1%_0.0625W_100PPM")
        (field (name "MANUFACTURER") "GENERIC")
        (field (name "AUTHOR") "CERN DEM JLC")
      )
      (libsource (lib "Resistors") (part "Resistor - 1%"))
    )
    (comp (ref "R4")
      (value "39")
      (footprint "RESC1005X40N")
      (description "Resistor - 1%")
      (fields
        (field (name "MANUFACTURER PART NUMBER") "R0402_39R_1%_0.0625W_100PPM")
        (field (name "MANUFACTURER") "GENERIC")
        (field (name "AUTHOR") "CERN DEM JLC")
      )
      (libsource (lib "Resistors") (part "Resistor - 1%"))
    )
    (comp (ref "R5")
      (value "39")
      (footprint "RESC1005X40N")
      (description "Resistor - 1%")
      (fields
        (field (name "MANUFACTURER PART NUMBER") "R0402_39R_1%_0.0625W_100PPM")
        (field (name "MANUFACTURER") "GENERIC")
        (field (name "AUTHOR") "CERN DEM JLC")
      )
      (libsource (lib "Resistors") (part "Resistor - 1%"))
    )
    (comp (ref "R6")
      (value "39")
      (footprint "RESC1005X40N")
      (description "Resistor - 1%")
      (fields
        (field (name "MANUFACTURER PART NUMBER") "R0402_39R_1%_0.0625W_100PPM")
        (field (name "MANUFACTURER") "GENERIC")
        (field (name "AUTHOR") "CERN DEM JLC")
      )
      (libsource (lib "Resistors") (part "Resistor - 1%"))
    )
    (comp (ref "R7")
      (value "39")
      (footprint "RESC1005X40N")
      (description "Resistor - 1%")
      (fields
        (field (name "MANUFACTURER PART NUMBER") "R0402_39R_1%_0.0625W_100PPM")
        (field (name "MANUFACTURER") "GENERIC")
        (field (name "AUTHOR") "CERN DEM JLC")
      )
      (libsource (lib "Resistors") (part "Resistor - 1%"))
    )
    (comp (ref "R8")
      (value "39")
      (footprint "RESC1005X40N")
      (description "Resistor - 1%")
      (fields
        (field (name "MANUFACTURER PART NUMBER") "R0402_39R_1%_0.0625W_100PPM")
        (field (name "MANUFACTURER") "GENERIC")
        (field (name "AUTHOR") "CERN DEM JLC")
      )
      (libsource (lib "Resistors") (part "Resistor - 1%"))
    )
    (comp (ref "R9")
      (value "39")
      (footprint "RESC1005X40N")
      (description "Resistor - 1%")
      (fields
        (field (name "MANUFACTURER PART NUMBER") "R0402_39R_1%_0.0625W_100PPM")
        (field (name "MANUFACTURER") "GENERIC")
        (field (name "AUTHOR") "CERN DEM JLC")
      )
      (libsource (lib "Resistors") (part "Resistor - 1%"))
    )
    (comp (ref "R10")
      (value "39")
      (footprint "RESC1005X40N")
      (description "Resistor - 1%")
      (fields
        (field (name "MANUFACTURER PART NUMBER") "R0402_39R_1%_0.0625W_100PPM")
        (field (name "MANUFACTURER") "GENERIC")
        (field (name "AUTHOR") "CERN DEM JLC")
      )
      (libsource (lib "Resistors") (part "Resistor - 1%"))
    )
    (comp (ref "R11")
      (value "39")
      (footprint "RESC1005X40N")
      (description "Resistor - 1%")
      (fields
        (field (name "MANUFACTURER PART NUMBER") "R0402_39R_1%_0.0625W_100PPM")
        (field (name "MANUFACTURER") "GENERIC")
        (field (name "AUTHOR") "CERN DEM JLC")
      )
      (libsource (lib "Resistors") (part "Resistor - 1%"))
    )
    (comp (ref "R12")
      (value "39")
      (footprint "RESC1005X40N")
      (description "Resistor - 1%")
      (fields
        (field (name "MANUFACTURER PART NUMBER") "R0402_39R_1%_0.0625W_100PPM")
        (field (name "MANUFACTURER") "GENERIC")
        (field (name "AUTHOR") "CERN DEM JLC")
      )
      (libsource (lib "Resistors") (part "Resistor - 1%"))
    )
    (comp (ref "R13")
      (value "39")
      (footprint "RESC1005X40N")
      (description "Resistor - 1%")
      (fields
        (field (name "MANUFACTURER PART NUMBER") "R0402_39R_1%_0.0625W_100PPM")
        (field (name "MANUFACTURER") "GENERIC")
        (field (name "AUTHOR") "CERN DEM JLC")
      )
      (libsource (lib "Resistors") (part "Resistor - 1%"))
    )
    (comp (ref "R14")
      (value "39")
      (footprint "RESC1005X40N")
      (description "Resistor - 1%")
      (fields
        (field (name "MANUFACTURER PART NUMBER") "R0402_39R_1%_0.0625W_100PPM")
        (field (name "MANUFACTURER") "GENERIC")
        (field (name "AUTHOR") "CERN DEM JLC")
      )
      (libsource (lib "Resistors") (part "Resistor - 1%"))
    )
    (comp (ref "R15")
      (value "39")
      (footprint "RESC1005X40N")
      (description "Resistor - 1%")
      (fields
        (field (name "MANUFACTURER PART NUMBER") "R0402_39R_1%_0.0625W_100PPM")
        (field (name "MANUFACTURER") "GENERIC")
        (field (name "AUTHOR") "CERN DEM JLC")
      )
      (libsource (lib "Resistors") (part "Resistor - 1%"))
    )
    (comp (ref "R16")
      (value "39")
      (footprint "RESC1005X40N")
      (description "Resistor - 1%")
      (fields
        (field (name "MANUFACTURER PART NUMBER") "R0402_39R_1%_0.0625W_100PPM")
        (field (name "MANUFACTURER") "GENERIC")
        (field (name "AUTHOR") "CERN DEM JLC")
      )
      (libsource (lib "Resistors") (part "Resistor - 1%"))
    )
    (comp (ref "R17")
      (value "39")
      (footprint "RESC1005X40N")
      (description "Resistor - 1%")
      (fields
        (field (name "MANUFACTURER PART NUMBER") "R0402_39R_1%_0.0625W_100PPM")
        (field (name "MANUFACTURER") "GENERIC")
        (field (name "AUTHOR") "CERN DEM JLC")
      )
      (libsource (lib "Resistors") (part "Resistor - 1%"))
    )
    (comp (ref "R18")
      (value "36")
      (footprint "RESC1005X40N")
      (description "Resistor - 1%")
      (fields
        (field (name "MANUFACTURER PART NUMBER") "R0402_36R_1%_0.0625W_100PPM")
        (field (name "MANUFACTURER") "GENERIC")
        (field (name "AUTHOR") "CERN DEM JLC")
      )
      (libsource (lib "Resistors") (part "Resistor - 1%"))
    )
    (comp (ref "R19")
      (value "36")
      (footprint "RESC1005X40N")
      (description "Resistor - 1%")
      (fields
        (field (name "MANUFACTURER PART NUMBER") "R0402_36R_1%_0.0625W_100PPM")
        (field (name "MANUFACTURER") "GENERIC")
        (field (name "AUTHOR") "CERN DEM JLC")
      )
      (libsource (lib "Resistors") (part "Resistor - 1%"))
    )
    (comp (ref "R20")
      (value "39")
      (footprint "RESC1005X40N")
      (description "Resistor - 1%")
      (fields
        (field (name "MANUFACTURER PART NUMBER") "R0402_39R_1%_0.0625W_100PPM")
        (field (name "MANUFACTURER") "GENERIC")
        (field (name "AUTHOR") "CERN DEM JLC")
      )
      (libsource (lib "Resistors") (part "Resistor - 1%"))
    )
    (comp (ref "R21")
      (value "1k")
      (footprint "RESC1005X40N")
      (description "Resistor - 1%")
      (fields
        (field (name "MANUFACTURER PART NUMBER") "R0402_1K_1%_0.0625W_100PPM")
        (field (name "MANUFACTURER") "GENERIC")
        (field (name "AUTHOR") "CERN DEM JLC")
      )
      (libsource (lib "Resistors") (part "Resistor - 1%"))
    )
    (comp (ref "R22")
      (value "39")
      (footprint "RESC1005X40N")
      (description "Resistor - 1%")
      (fields
        (field (name "MANUFACTURER PART NUMBER") "R0402_39R_1%_0.0625W_100PPM")
        (field (name "MANUFACTURER") "GENERIC")
        (field (name "AUTHOR") "CERN DEM JLC")
      )
      (libsource (lib "Resistors") (part "Resistor - 1%"))
    )
    (comp (ref "R23")
      (value "39")
      (footprint "RESC1005X40N")
      (description "Resistor - 1%")
      (fields
        (field (name "MANUFACTURER PART NUMBER") "R0402_39R_1%_0.0625W_100PPM")
        (field (name "MANUFACTURER") "GENERIC")
        (field (name "AUTHOR") "CERN DEM JLC")
      )
      (libsource (lib "Resistors") (part "Resistor - 1%"))
    )
    (comp (ref "R24")
      (value "39")
      (footprint "RESC1005X40N")
      (description "Resistor - 1%")
      (fields
        (field (name "MANUFACTURER PART NUMBER") "R0402_39R_1%_0.0625W_100PPM")
        (field (name "MANUFACTURER") "GENERIC")
        (field (name "AUTHOR") "CERN DEM JLC")
      )
      (libsource (lib "Resistors") (part "Resistor - 1%"))
    )
    (comp (ref "R25")
      (value "499")
      (footprint "RESC1005X40N")
      (description "Resistor - 1%")
      (fields
        (field (name "PART NUMBER") "R0402_499R_1%_0.0625W_100PPM")
        (field (name "POWER") "0.0625W")
        (field (name "AUTHOR") "CERN DEM BC")
      )
      (libsource (lib "Resistors") (part "Resistor - 1%"))
    )
    (comp (ref "R26")
      (value "39")
      (footprint "RESC1005X40N")
      (description "Resistor - 1%")
      (fields
        (field (name "MANUFACTURER PART NUMBER") "R0402_39R_1%_0.0625W_100PPM")
        (field (name "MANUFACTURER") "GENERIC")
        (field (name "AUTHOR") "CERN DEM JLC")
      )
      (libsource (lib "Resistors") (part "Resistor - 1%"))
    )
    (comp (ref "R27")
      (value "240")
      (footprint "RESC1005X40N")
      (description "Resistor - 1%")
      (fields
        (field (name "MANUFACTURER PART NUMBER") "R0402_240R_1%_0.0625W_100PPM")
        (field (name "MANUFACTURER") "GENERIC")
        (field (name "AUTHOR") "CERN DEM JLC")
      )
      (libsource (lib "Resistors") (part "Resistor - 1%"))
    )
    (comp (ref "R28")
      (value "39")
      (footprint "RESC1005X40N")
      (description "Resistor - 1%")
      (fields
        (field (name "MANUFACTURER PART NUMBER") "R0402_39R_1%_0.0625W_100PPM")
        (field (name "MANUFACTURER") "GENERIC")
        (field (name "AUTHOR") "CERN DEM JLC")
      )
      (libsource (lib "Resistors") (part "Resistor - 1%"))
    )
    (comp (ref "R29")
      (value "240")
      (footprint "RESC1005X40N")
      (description "Resistor - 1%")
      (fields
        (field (name "MANUFACTURER PART NUMBER") "R0402_240R_1%_0.0625W_100PPM")
        (field (name "MANUFACTURER") "GENERIC")
        (field (name "AUTHOR") "CERN DEM JLC")
      )
      (libsource (lib "Resistors") (part "Resistor - 1%"))
    )
    (comp (ref "R30")
      (value "4k7")
      (footprint "RESC1005X40N")
      (description "Resistor - 1%")
      (fields
        (field (name "MANUFACTURER PART NUMBER") "R0402_4K7_1%_0.0625W_100PPM")
        (field (name "MANUFACTURER") "GENERIC")
        (field (name "AUTHOR") "CERN DEM JLC")
      )
      (libsource (lib "Resistors") (part "Resistor - 1%"))
    )
    (comp (ref "R31")
      (value "39")
      (footprint "RESC1005X40N")
      (description "Resistor - 1%")
      (fields
        (field (name "MANUFACTURER PART NUMBER") "R0402_39R_1%_0.0625W_100PPM")
        (field (name "MANUFACTURER") "GENERIC")
        (field (name "AUTHOR") "CERN DEM JLC")
      )
      (libsource (lib "Resistors") (part "Resistor - 1%"))
    )
    (comp (ref "R32")
      (value "39")
      (footprint "RESC1005X40N")
      (description "Resistor - 1%")
      (fields
        (field (name "MANUFACTURER PART NUMBER") "R0402_39R_1%_0.0625W_100PPM")
        (field (name "MANUFACTURER") "GENERIC")
        (field (name "AUTHOR") "CERN DEM JLC")
      )
      (libsource (lib "Resistors") (part "Resistor - 1%"))
    )
    (comp (ref "R33")
      (value "240")
      (footprint "RESC1005X40N")
      (description "Resistor - 1%")
      (fields
        (field (name "MANUFACTURER PART NUMBER") "R0402_240R_1%_0.0625W_100PPM")
        (field (name "MANUFACTURER") "GENERIC")
        (field (name "AUTHOR") "CERN DEM JLC")
      )
      (libsource (lib "Resistors") (part "Resistor - 1%"))
    )
    (comp (ref "R34")
      (value "240")
      (footprint "RESC1005X40N")
      (description "Resistor - 1%")
      (fields
        (field (name "MANUFACTURER PART NUMBER") "R0402_240R_1%_0.0625W_100PPM")
        (field (name "MANUFACTURER") "GENERIC")
        (field (name "AUTHOR") "CERN DEM JLC")
      )
      (libsource (lib "Resistors") (part "Resistor - 1%"))
    )
    (comp (ref "R35")
      (value "100")
      (footprint "RESC1005X40N")
      (description "Resistor - 1%")
      (fields
        (field (name "MANUFACTURER PART NUMBER") "R0402_100R_1%_0.0625W_100PPM")
        (field (name "MANUFACTURER") "GENERIC")
        (field (name "AUTHOR") "CERN DEM JLC")
      )
      (libsource (lib "Resistors") (part "Resistor - 1%"))
    )
    (comp (ref "R36")
      (value "100")
      (footprint "RESC1005X40N")
      (description "Resistor - 1%")
      (fields
        (field (name "MANUFACTURER PART NUMBER") "R0402_100R_1%_0.0625W_100PPM")
        (field (name "MANUFACTURER") "GENERIC")
        (field (name "AUTHOR") "CERN DEM JLC")
      )
      (libsource (lib "Resistors") (part "Resistor - 1%"))
    )
    (comp (ref "R38")
      (value "100")
      (footprint "RESC1005X40N")
      (description "Resistor - 1%")
      (fields
        (field (name "MANUFACTURER PART NUMBER") "R0402_100R_1%_0.0625W_100PPM")
        (field (name "MANUFACTURER") "GENERIC")
        (field (name "AUTHOR") "CERN DEM JLC")
      )
      (libsource (lib "Resistors") (part "Resistor - 1%"))
    )
    (comp (ref "R39")
      (value "100")
      (footprint "RESC1005X40N")
      (description "Resistor - 1%")
      (fields
        (field (name "MANUFACTURER PART NUMBER") "R0402_100R_1%_0.0625W_100PPM")
        (field (name "MANUFACTURER") "GENERIC")
        (field (name "AUTHOR") "CERN DEM JLC")
      )
      (libsource (lib "Resistors") (part "Resistor - 1%"))
    )
    (comp (ref "R40")
      (value "100")
      (footprint "RESC1005X40N")
      (description "Resistor - 1%")
      (fields
        (field (name "MANUFACTURER PART NUMBER") "R0402_100R_1%_0.0625W_100PPM")
        (field (name "MANUFACTURER") "GENERIC")
        (field (name "AUTHOR") "CERN DEM JLC")
      )
      (libsource (lib "Resistors") (part "Resistor - 1%"))
    )
    (comp (ref "R41")
      (value "100")
      (footprint "RESC1005X40N")
      (description "Resistor - 1%")
      (fields
        (field (name "MANUFACTURER PART NUMBER") "R0402_100R_1%_0.0625W_100PPM")
        (field (name "MANUFACTURER") "GENERIC")
        (field (name "AUTHOR") "CERN DEM JLC")
      )
      (libsource (lib "Resistors") (part "Resistor - 1%"))
    )
    (comp (ref "R42")
      (value "100")
      (footprint "RESC1005X40N")
      (description "Resistor - 1%")
      (fields
        (field (name "MANUFACTURER PART NUMBER") "R0402_100R_1%_0.0625W_100PPM")
        (field (name "MANUFACTURER") "GENERIC")
        (field (name "AUTHOR") "CERN DEM JLC")
      )
      (libsource (lib "Resistors") (part "Resistor - 1%"))
    )
    (comp (ref "R43")
      (value "100")
      (footprint "RESC1005X40N")
      (description "Resistor - 1%")
      (fields
        (field (name "MANUFACTURER PART NUMBER") "R0402_100R_1%_0.0625W_100PPM")
        (field (name "MANUFACTURER") "GENERIC")
        (field (name "AUTHOR") "CERN DEM JLC")
      )
      (libsource (lib "Resistors") (part "Resistor - 1%"))
    )
    (comp (ref "R44")
      (value "10k")
      (footprint "RESC1005X40N")
      (description "Resistor - 1%")
      (fields
        (field (name "MANUFACTURER PART NUMBER") "R0402_10K_1%_0.0625W_100PPM")
        (field (name "MANUFACTURER") "GENERIC")
        (field (name "AUTHOR") "CERN DEM JLC")
      )
      (libsource (lib "Resistors") (part "Resistor - 1%"))
    )
    (comp (ref "R45")
      (value "10")
      (footprint "RESC1005X40N")
      (description "Resistor - 1%")
      (fields
        (field (name "MANUFACTURER PART NUMBER") "R0402_10R_1%_0.0625W_200PPM")
        (field (name "MANUFACTURER") "GENERIC")
        (field (name "AUTHOR") "CERN DEM JLC")
      )
      (libsource (lib "Resistors") (part "Resistor - 1%"))
    )
    (comp (ref "R46")
      (value "10k")
      (footprint "RESC1005X40N")
      (description "Resistor - 1%")
      (fields
        (field (name "MANUFACTURER PART NUMBER") "R0402_10K_1%_0.0625W_100PPM")
        (field (name "MANUFACTURER") "GENERIC")
        (field (name "AUTHOR") "CERN DEM JLC")
      )
      (libsource (lib "Resistors") (part "Resistor - 1%"))
    )
  )
  (nets
    (net (code "2") (name "/DDR4_A0") (class "Default")
      (node (ref "IC1") (pin "P3") (pinfunction "A0_P3") (pintype "input"))
      (node (ref "IC2") (pin "P3") (pinfunction "A0_P3") (pintype "input"))
      (node (ref "IC3") (pin "P3") (pinfunction "A0_P3") (pintype "input"))
      (node (ref "IC4") (pin "P3") (pinfunction "A0_P3") (pintype "input"))
      (node (ref "R1") (pin "2") (pinfunction "2_2") (pintype "passive"))
    )
    (net (code "3") (name "/DDR4_A1") (class "Default")
      (node (ref "IC1") (pin "P7") (pinfunction "A1_P7") (pintype "input"))
      (node (ref "IC2") (pin "P7") (pinfunction "A1_P7") (pintype "input"))
      (node (ref "IC3") (pin "P7") (pinfunction "A1_P7") (pintype "input"))
      (node (ref "IC4") (pin "P7") (pinfunction "A1_P7") (pintype "input"))
      (node (ref "R2") (pin "2") (pinfunction "2_2") (pintype "passive"))
    )
    (net (code "4") (name "/DDR4_A2") (class "Default")
      (node (ref "IC1") (pin "R3") (pinfunction "A2_R3") (pintype "input"))
      (node (ref "IC2") (pin "R3") (pinfunction "A2_R3") (pintype "input"))
      (node (ref "IC3") (pin "R3") (pinfunction "A2_R3") (pintype "input"))
      (node (ref "IC4") (pin "R3") (pinfunction "A2_R3") (pintype "input"))
      (node (ref "R3") (pin "2") (pinfunction "2_2") (pintype "passive"))
    )
    (net (code "5") (name "/DDR4_A3") (class "Default")
      (node (ref "IC1") (pin "N7") (pinfunction "A3_N7") (pintype "input"))
      (node (ref "IC2") (pin "N7") (pinfunction "A3_N7") (pintype "input"))
      (node (ref "IC3") (pin "N7") (pinfunction "A3_N7") (pintype "input"))
      (node (ref "IC4") (pin "N7") (pinfunction "A3_N7") (pintype "input"))
      (node (ref "R4") (pin "2") (pinfunction "2_2") (pintype "passive"))
    )
    (net (code "6") (name "/DDR4_A4") (class "Default")
      (node (ref "IC1") (pin "N3") (pinfunction "A4_N3") (pintype "input"))
      (node (ref "IC2") (pin "N3") (pinfunction "A4_N3") (pintype "input"))
      (node (ref "IC3") (pin "N3") (pinfunction "A4_N3") (pintype "input"))
      (node (ref "IC4") (pin "N3") (pinfunction "A4_N3") (pintype "input"))
      (node (ref "R5") (pin "2") (pinfunction "2_2") (pintype "passive"))
    )
    (net (code "7") (name "/DDR4_A5") (class "Default")
      (node (ref "IC1") (pin "P8") (pinfunction "A5_P8") (pintype "input"))
      (node (ref "IC2") (pin "P8") (pinfunction "A5_P8") (pintype "input"))
      (node (ref "IC3") (pin "P8") (pinfunction "A5_P8") (pintype "input"))
      (node (ref "IC4") (pin "P8") (pinfunction "A5_P8") (pintype "input"))
      (node (ref "R6") (pin "2") (pinfunction "2_2") (pintype "passive"))
    )
    (net (code "8") (name "/DDR4_A6") (class "Default")
      (node (ref "IC1") (pin "P2") (pinfunction "A6_P2") (pintype "input"))
      (node (ref "IC2") (pin "P2") (pinfunction "A6_P2") (pintype "input"))
      (node (ref "IC3") (pin "P2") (pinfunction "A6_P2") (pintype "input"))
      (node (ref "IC4") (pin "P2") (pinfunction "A6_P2") (pintype "input"))
      (node (ref "R7") (pin "2") (pinfunction "2_2") (pintype "passive"))
    )
    (net (code "9") (name "/DDR4_A7") (class "Default")
      (node (ref "IC1") (pin "R8") (pinfunction "A7_R8") (pintype "input"))
      (node (ref "IC2") (pin "R8") (pinfunction "A7_R8") (pintype "input"))
      (node (ref "IC3") (pin "R8") (pinfunction "A7_R8") (pintype "input"))
      (node (ref "IC4") (pin "R8") (pinfunction "A7_R8") (pintype "input"))
      (node (ref "R8") (pin "2") (pinfunction "2_2") (pintype "passive"))
    )
    (net (code "10") (name "/DDR4_A8") (class "Default")
      (node (ref "IC1") (pin "R2") (pinfunction "A8_R2") (pintype "input"))
      (node (ref "IC2") (pin "R2") (pinfunction "A8_R2") (pintype "input"))
      (node (ref "IC3") (pin "R2") (pinfunction "A8_R2") (pintype "input"))
      (node (ref "IC4") (pin "R2") (pinfunction "A8_R2") (pintype "input"))
      (node (ref "R9") (pin "2") (pinfunction "2_2") (pintype "passive"))
    )
    (net (code "11") (name "/DDR4_A9") (class "Default")
      (node (ref "IC1") (pin "R7") (pinfunction "A9_R7") (pintype "input"))
      (node (ref "IC2") (pin "R7") (pinfunction "A9_R7") (pintype "input"))
      (node (ref "IC3") (pin "R7") (pinfunction "A9_R7") (pintype "input"))
      (node (ref "IC4") (pin "R7") (pinfunction "A9_R7") (pintype "input"))
      (node (ref "R10") (pin "2") (pinfunction "2_2") (pintype "passive"))
    )
    (net (code "12") (name "/DDR4_A10") (class "Default")
      (node (ref "IC1") (pin "M3") (pinfunction "A10/AP_M3") (pintype "input"))
      (node (ref "IC2") (pin "M3") (pinfunction "A10/AP_M3") (pintype "input"))
      (node (ref "IC3") (pin "M3") (pinfunction "A10/AP_M3") (pintype "input"))
      (node (ref "IC4") (pin "M3") (pinfunction "A10/AP_M3") (pintype "input"))
      (node (ref "R11") (pin "2") (pinfunction "2_2") (pintype "passive"))
    )
    (net (code "13") (name "/DDR4_A11") (class "Default")
      (node (ref "IC1") (pin "T2") (pinfunction "A11_T2") (pintype "input"))
      (node (ref "IC2") (pin "T2") (pinfunction "A11_T2") (pintype "input"))
      (node (ref "IC3") (pin "T2") (pinfunction "A11_T2") (pintype "input"))
      (node (ref "IC4") (pin "T2") (pinfunction "A11_T2") (pintype "input"))
      (node (ref "R12") (pin "2") (pinfunction "2_2") (pintype "passive"))
    )
    (net (code "14") (name "/DDR4_A12") (class "Default")
      (node (ref "IC1") (pin "M7") (pinfunction "A12/~{BC}_M7") (pintype "input"))
      (node (ref "IC2") (pin "M7") (pinfunction "A12/~{BC}_M7") (pintype "input"))
      (node (ref "IC3") (pin "M7") (pinfunction "A12/~{BC}_M7") (pintype "input"))
      (node (ref "IC4") (pin "M7") (pinfunction "A12/~{BC}_M7") (pintype "input"))
      (node (ref "R13") (pin "2") (pinfunction "2_2") (pintype "passive"))
    )
    (net (code "15") (name "/DDR4_A13") (class "Default")
      (node (ref "IC1") (pin "T8") (pinfunction "A13_T8") (pintype "input"))
      (node (ref "IC2") (pin "T8") (pinfunction "A13_T8") (pintype "input"))
      (node (ref "IC3") (pin "T8") (pinfunction "A13_T8") (pintype "input"))
      (node (ref "IC4") (pin "T8") (pinfunction "A13_T8") (pintype "input"))
      (node (ref "R14") (pin "2") (pinfunction "2_2") (pintype "passive"))
    )
    (net (code "16") (name "/DDR4_A14_WE_B") (class "Default")
      (node (ref "IC1") (pin "L2") (pinfunction "A14/~{WE}_L2") (pintype "input"))
      (node (ref "IC2") (pin "L2") (pinfunction "A14/~{WE}_L2") (pintype "input"))
      (node (ref "IC3") (pin "L2") (pinfunction "A14/~{WE}_L2") (pintype "input"))
      (node (ref "IC4") (pin "L2") (pinfunction "A14/~{WE}_L2") (pintype "input"))
      (node (ref "R15") (pin "2") (pinfunction "2_2") (pintype "passive"))
    )
    (net (code "17") (name "/DDR4_A15_CAS_B") (class "Default")
      (node (ref "IC1") (pin "M8") (pinfunction "A15/~{CAS}_M8") (pintype "input"))
      (node (ref "IC2") (pin "M8") (pinfunction "A15/~{CAS}_M8") (pintype "input"))
      (node (ref "IC3") (pin "M8") (pinfunction "A15/~{CAS}_M8") (pintype "input"))
      (node (ref "IC4") (pin "M8") (pinfunction "A15/~{CAS}_M8") (pintype "input"))
      (node (ref "R16") (pin "2") (pinfunction "2_2") (pintype "passive"))
    )
    (net (code "18") (name "/DDR4_A16_RAS_B") (class "Default")
      (node (ref "IC1") (pin "L8") (pinfunction "A16/~{RAS}_L8") (pintype "input"))
      (node (ref "IC2") (pin "L8") (pinfunction "A16/~{RAS}_L8") (pintype "input"))
      (node (ref "IC3") (pin "L8") (pinfunction "A16/~{RAS}_L8") (pintype "input"))
      (node (ref "IC4") (pin "L8") (pinfunction "A16/~{RAS}_L8") (pintype "input"))
      (node (ref "R17") (pin "2") (pinfunction "2_2") (pintype "passive"))
    )
    (net (code "19") (name "/DDR4_ACT_B") (class "Default")
      (node (ref "IC1") (pin "L3") (pinfunction "~{ACT}_L3") (pintype "input"))
      (node (ref "IC2") (pin "L3") (pinfunction "~{ACT}_L3") (pintype "input"))
      (node (ref "IC3") (pin "L3") (pinfunction "~{ACT}_L3") (pintype "input"))
      (node (ref "IC4") (pin "L3") (pinfunction "~{ACT}_L3") (pintype "input"))
      (node (ref "R22") (pin "2") (pinfunction "2_2") (pintype "passive"))
    )
    (net (code "20") (name "/DDR4_ALERT_B") (class "Default")
      (node (ref "IC1") (pin "P9") (pinfunction "~{ALERT}_P9") (pintype "output"))
      (node (ref "IC2") (pin "P9") (pinfunction "~{ALERT}_P9") (pintype "output"))
      (node (ref "IC3") (pin "P9") (pinfunction "~{ALERT}_P9") (pintype "output"))
      (node (ref "IC4") (pin "P9") (pinfunction "~{ALERT}_P9") (pintype "output"))
      (node (ref "R30") (pin "2") (pinfunction "2_2") (pintype "passive"))
    )
    (net (code "21") (name "/DDR4_BA0") (class "Default")
      (node (ref "IC1") (pin "N2") (pinfunction "BA0_N2") (pintype "input"))
      (node (ref "IC2") (pin "N2") (pinfunction "BA0_N2") (pintype "input"))
      (node (ref "IC3") (pin "N2") (pinfunction "BA0_N2") (pintype "input"))
      (node (ref "IC4") (pin "N2") (pinfunction "BA0_N2") (pintype "input"))
      (node (ref "R28") (pin "2") (pinfunction "2_2") (pintype "passive"))
    )
    (net (code "22") (name "/DDR4_BA1") (class "Default")
      (node (ref "IC1") (pin "N8") (pinfunction "BA1_N8") (pintype "input"))
      (node (ref "IC2") (pin "N8") (pinfunction "BA1_N8") (pintype "input"))
      (node (ref "IC3") (pin "N8") (pinfunction "BA1_N8") (pintype "input"))
      (node (ref "IC4") (pin "N8") (pinfunction "BA1_N8") (pintype "input"))
      (node (ref "R31") (pin "2") (pinfunction "2_2") (pintype "passive"))
    )
    (net (code "23") (name "/DDR4_BG0") (class "Default")
      (node (ref "IC1") (pin "M2") (pinfunction "BG0_M2") (pintype "input"))
      (node (ref "IC2") (pin "M2") (pinfunction "BG0_M2") (pintype "input"))
      (node (ref "IC3") (pin "M2") (pinfunction "BG0_M2") (pintype "input"))
      (node (ref "IC4") (pin "M2") (pinfunction "BG0_M2") (pintype "input"))
      (node (ref "R32") (pin "2") (pinfunction "2_2") (pintype "passive"))
    )
    (net (code "24") (name "/DDR4_CKE") (class "Default")
      (node (ref "IC1") (pin "K2") (pinfunction "CKE_K2") (pintype "input"))
      (node (ref "IC2") (pin "K2") (pinfunction "CKE_K2") (pintype "input"))
      (node (ref "IC3") (pin "K2") (pinfunction "CKE_K2") (pintype "input"))
      (node (ref "IC4") (pin "K2") (pinfunction "CKE_K2") (pintype "input"))
      (node (ref "R20") (pin "2") (pinfunction "2_2") (pintype "passive"))
    )
    (net (code "25") (name "/DDR4_CK_N") (class "Default")
      (node (ref "IC1") (pin "K8") (pinfunction "CK_c_K8") (pintype "input"))
      (node (ref "IC2") (pin "K8") (pinfunction "CK_c_K8") (pintype "input"))
      (node (ref "IC3") (pin "K8") (pinfunction "CK_c_K8") (pintype "input"))
      (node (ref "IC4") (pin "K8") (pinfunction "CK_c_K8") (pintype "input"))
      (node (ref "R19") (pin "2") (pinfunction "2_2") (pintype "passive"))
    )
    (net (code "26") (name "/DDR4_CK_P") (class "Default")
      (node (ref "IC1") (pin "K7") (pinfunction "CK_t_K7") (pintype "input"))
      (node (ref "IC2") (pin "K7") (pinfunction "CK_t_K7") (pintype "input"))
      (node (ref "IC3") (pin "K7") (pinfunction "CK_t_K7") (pintype "input"))
      (node (ref "IC4") (pin "K7") (pinfunction "CK_t_K7") (pintype "input"))
      (node (ref "R18") (pin "2") (pinfunction "2_2") (pintype "passive"))
    )
    (net (code "27") (name "/DDR4_CS_B") (class "Default")
      (node (ref "IC1") (pin "L7") (pinfunction "~{CS}_L7") (pintype "input"))
      (node (ref "IC2") (pin "L7") (pinfunction "~{CS}_L7") (pintype "input"))
      (node (ref "IC3") (pin "L7") (pinfunction "~{CS}_L7") (pintype "input"))
      (node (ref "IC4") (pin "L7") (pinfunction "~{CS}_L7") (pintype "input"))
      (node (ref "R24") (pin "2") (pinfunction "2_2") (pintype "passive"))
    )
    (net (code "28") (name "/DDR4_DM0") (class "Default")
      (node (ref "IC1") (pin "E7") (pinfunction "NF/~{LDM}/~{LDBI}_E7") (pintype "input"))
    )
    (net (code "29") (name "/DDR4_DM1") (class "Default")
      (node (ref "IC1") (pin "E2") (pinfunction "NF/~{UDM}/~{UDBI}_E2") (pintype "input"))
    )
    (net (code "30") (name "/DDR4_DM2") (class "Default")
      (node (ref "IC2") (pin "E7") (pinfunction "NF/~{LDM}/~{LDBI}_E7") (pintype "input"))
    )
    (net (code "31") (name "/DDR4_DM3") (class "Default")
      (node (ref "IC2") (pin "E2") (pinfunction "NF/~{UDM}/~{UDBI}_E2") (pintype "input"))
    )
    (net (code "32") (name "/DDR4_DM4") (class "Default")
      (node (ref "IC3") (pin "E7") (pinfunction "NF/~{LDM}/~{LDBI}_E7") (pintype "input"))
    )
    (net (code "33") (name "/DDR4_DM5") (class "Default")
      (node (ref "IC3") (pin "E2") (pinfunction "NF/~{UDM}/~{UDBI}_E2") (pintype "input"))
    )
    (net (code "34") (name "/DDR4_DM6") (class "Default")
      (node (ref "IC4") (pin "E7") (pinfunction "NF/~{LDM}/~{LDBI}_E7") (pintype "input"))
    )
    (net (code "35") (name "/DDR4_DM7") (class "Default")
      (node (ref "IC4") (pin "E2") (pinfunction "NF/~{UDM}/~{UDBI}_E2") (pintype "input"))
    )
    (net (code "37") (name "/DDR4_DQ0") (class "Default")
      (node (ref "IC1") (pin "G2") (pinfunction "DQ0_G2") (pintype "bidirectional"))
    )
    (net (code "38") (name "/DDR4_DQ1") (class "Default")
      (node (ref "IC1") (pin "F7") (pinfunction "DQ1_F7") (pintype "bidirectional"))
    )
    (net (code "39") (name "/DDR4_DQ2") (class "Default")
      (node (ref "IC1") (pin "H3") (pinfunction "DQ2_H3") (pintype "bidirectional"))
    )
    (net (code "40") (name "/DDR4_DQ3") (class "Default")
      (node (ref "IC1") (pin "H7") (pinfunction "DQ3_H7") (pintype "bidirectional"))
    )
    (net (code "41") (name "/DDR4_DQ4") (class "Default")
      (node (ref "IC1") (pin "H2") (pinfunction "DQ4_H2") (pintype "bidirectional"))
    )
    (net (code "42") (name "/DDR4_DQ5") (class "Default")
      (node (ref "IC1") (pin "H8") (pinfunction "DQ5_H8") (pintype "bidirectional"))
    )
    (net (code "43") (name "/DDR4_DQ6") (class "Default")
      (node (ref "IC1") (pin "J3") (pinfunction "DQ6_J3") (pintype "bidirectional"))
    )
    (net (code "44") (name "/DDR4_DQ7") (class "Default")
      (node (ref "IC1") (pin "J7") (pinfunction "DQ7_J7") (pintype "bidirectional"))
    )
    (net (code "45") (name "/DDR4_DQ8") (class "Default")
      (node (ref "IC1") (pin "A3") (pinfunction "DQ8_A3") (pintype "bidirectional"))
    )
    (net (code "46") (name "/DDR4_DQ9") (class "Default")
      (node (ref "IC1") (pin "B8") (pinfunction "DQ9_B8") (pintype "bidirectional"))
    )
    (net (code "47") (name "/DDR4_DQ10") (class "Default")
      (node (ref "IC1") (pin "C3") (pinfunction "DQ10_C3") (pintype "bidirectional"))
    )
    (net (code "48") (name "/DDR4_DQ11") (class "Default")
      (node (ref "IC1") (pin "C7") (pinfunction "DQ11_C7") (pintype "bidirectional"))
    )
    (net (code "49") (name "/DDR4_DQ12") (class "Default")
      (node (ref "IC1") (pin "C2") (pinfunction "DQ12_C2") (pintype "bidirectional"))
    )
    (net (code "50") (name "/DDR4_DQ13") (class "Default")
      (node (ref "IC1") (pin "C8") (pinfunction "DQ13_C8") (pintype "bidirectional"))
    )
    (net (code "51") (name "/DDR4_DQ14") (class "Default")
      (node (ref "IC1") (pin "D3") (pinfunction "DQ14_D3") (pintype "bidirectional"))
    )
    (net (code "52") (name "/DDR4_DQ15") (class "Default")
      (node (ref "IC1") (pin "D7") (pinfunction "DQ15_D7") (pintype "bidirectional"))
    )
    (net (code "53") (name "/DDR4_DQ16") (class "Default")
      (node (ref "IC2") (pin "G2") (pinfunction "DQ0_G2") (pintype "bidirectional"))
    )
    (net (code "54") (name "/DDR4_DQ17") (class "Default")
      (node (ref "IC2") (pin "F7") (pinfunction "DQ1_F7") (pintype "bidirectional"))
    )
    (net (code "55") (name "/DDR4_DQ18") (class "Default")
      (node (ref "IC2") (pin "H3") (pinfunction "DQ2_H3") (pintype "bidirectional"))
    )
    (net (code "56") (name "/DDR4_DQ19") (class "Default")
      (node (ref "IC2") (pin "H7") (pinfunction "DQ3_H7") (pintype "bidirectional"))
    )
    (net (code "57") (name "/DDR4_DQ20") (class "Default")
      (node (ref "IC2") (pin "H2") (pinfunction "DQ4_H2") (pintype "bidirectional"))
    )
    (net (code "58") (name "/DDR4_DQ21") (class "Default")
      (node (ref "IC2") (pin "H8") (pinfunction "DQ5_H8") (pintype "bidirectional"))
    )
    (net (code "59") (name "/DDR4_DQ22") (class "Default")
      (node (ref "IC2") (pin "J3") (pinfunction "DQ6_J3") (pintype "bidirectional"))
    )
    (net (code "60") (name "/DDR4_DQ23") (class "Default")
      (node (ref "IC2") (pin "J7") (pinfunction "DQ7_J7") (pintype "bidirectional"))
    )
    (net (code "61") (name "/DDR4_DQ24") (class "Default")
      (node (ref "IC2") (pin "A3") (pinfunction "DQ8_A3") (pintype "bidirectional"))
    )
    (net (code "62") (name "/DDR4_DQ25") (class "Default")
      (node (ref "IC2") (pin "B8") (pinfunction "DQ9_B8") (pintype "bidirectional"))
    )
    (net (code "63") (name "/DDR4_DQ26") (class "Default")
      (node (ref "IC2") (pin "C3") (pinfunction "DQ10_C3") (pintype "bidirectional"))
    )
    (net (code "64") (name "/DDR4_DQ27") (class "Default")
      (node (ref "IC2") (pin "C7") (pinfunction "DQ11_C7") (pintype "bidirectional"))
    )
    (net (code "65") (name "/DDR4_DQ28") (class "Default")
      (node (ref "IC2") (pin "C2") (pinfunction "DQ12_C2") (pintype "bidirectional"))
    )
    (net (code "66") (name "/DDR4_DQ29") (class "Default")
      (node (ref "IC2") (pin "C8") (pinfunction "DQ13_C8") (pintype "bidirectional"))
    )
    (net (code "67") (name "/DDR4_DQ30") (class "Default")
      (node (ref "IC2") (pin "D3") (pinfunction "DQ14_D3") (pintype "bidirectional"))
    )
    (net (code "68") (name "/DDR4_DQ31") (class "Default")
      (node (ref "IC2") (pin "D7") (pinfunction "DQ15_D7") (pintype "bidirectional"))
    )
    (net (code "69") (name "/DDR4_DQ32") (class "Default")
      (node (ref "IC3") (pin "G2") (pinfunction "DQ0_G2") (pintype "bidirectional"))
    )
    (net (code "70") (name "/DDR4_DQ33") (class "Default")
      (node (ref "IC3") (pin "F7") (pinfunction "DQ1_F7") (pintype "bidirectional"))
    )
    (net (code "71") (name "/DDR4_DQ34") (class "Default")
      (node (ref "IC3") (pin "H3") (pinfunction "DQ2_H3") (pintype "bidirectional"))
    )
    (net (code "72") (name "/DDR4_DQ35") (class "Default")
      (node (ref "IC3") (pin "H7") (pinfunction "DQ3_H7") (pintype "bidirectional"))
    )
    (net (code "73") (name "/DDR4_DQ36") (class "Default")
      (node (ref "IC3") (pin "H2") (pinfunction "DQ4_H2") (pintype "bidirectional"))
    )
    (net (code "74") (name "/DDR4_DQ37") (class "Default")
      (node (ref "IC3") (pin "H8") (pinfunction "DQ5_H8") (pintype "bidirectional"))
    )
    (net (code "75") (name "/DDR4_DQ38") (class "Default")
      (node (ref "IC3") (pin "J3") (pinfunction "DQ6_J3") (pintype "bidirectional"))
    )
    (net (code "76") (name "/DDR4_DQ39") (class "Default")
      (node (ref "IC3") (pin "J7") (pinfunction "DQ7_J7") (pintype "bidirectional"))
    )
    (net (code "77") (name "/DDR4_DQ40") (class "Default")
      (node (ref "IC3") (pin "A3") (pinfunction "DQ8_A3") (pintype "bidirectional"))
    )
    (net (code "78") (name "/DDR4_DQ41") (class "Default")
      (node (ref "IC3") (pin "B8") (pinfunction "DQ9_B8") (pintype "bidirectional"))
    )
    (net (code "79") (name "/DDR4_DQ42") (class "Default")
      (node (ref "IC3") (pin "C3") (pinfunction "DQ10_C3") (pintype "bidirectional"))
    )
    (net (code "80") (name "/DDR4_DQ43") (class "Default")
      (node (ref "IC3") (pin "C7") (pinfunction "DQ11_C7") (pintype "bidirectional"))
    )
    (net (code "81") (name "/DDR4_DQ44") (class "Default")
      (node (ref "IC3") (pin "C2") (pinfunction "DQ12_C2") (pintype "bidirectional"))
    )
    (net (code "82") (name "/DDR4_DQ45") (class "Default")
      (node (ref "IC3") (pin "C8") (pinfunction "DQ13_C8") (pintype "bidirectional"))
    )
    (net (code "83") (name "/DDR4_DQ46") (class "Default")
      (node (ref "IC3") (pin "D3") (pinfunction "DQ14_D3") (pintype "bidirectional"))
    )
    (net (code "84") (name "/DDR4_DQ47") (class "Default")
      (node (ref "IC3") (pin "D7") (pinfunction "DQ15_D7") (pintype "bidirectional"))
    )
    (net (code "85") (name "/DDR4_DQ48") (class "Default")
      (node (ref "IC4") (pin "G2") (pinfunction "DQ0_G2") (pintype "bidirectional"))
    )
    (net (code "86") (name "/DDR4_DQ49") (class "Default")
      (node (ref "IC4") (pin "F7") (pinfunction "DQ1_F7") (pintype "bidirectional"))
    )
    (net (code "87") (name "/DDR4_DQ50") (class "Default")
      (node (ref "IC4") (pin "H3") (pinfunction "DQ2_H3") (pintype "bidirectional"))
    )
    (net (code "88") (name "/DDR4_DQ51") (class "Default")
      (node (ref "IC4") (pin "H7") (pinfunction "DQ3_H7") (pintype "bidirectional"))
    )
    (net (code "89") (name "/DDR4_DQ52") (class "Default")
      (node (ref "IC4") (pin "H2") (pinfunction "DQ4_H2") (pintype "bidirectional"))
    )
    (net (code "90") (name "/DDR4_DQ53") (class "Default")
      (node (ref "IC4") (pin "H8") (pinfunction "DQ5_H8") (pintype "bidirectional"))
    )
    (net (code "91") (name "/DDR4_DQ54") (class "Default")
      (node (ref "IC4") (pin "J3") (pinfunction "DQ6_J3") (pintype "bidirectional"))
    )
    (net (code "92") (name "/DDR4_DQ55") (class "Default")
      (node (ref "IC4") (pin "J7") (pinfunction "DQ7_J7") (pintype "bidirectional"))
    )
    (net (code "93") (name "/DDR4_DQ56") (class "Default")
      (node (ref "IC4") (pin "A3") (pinfunction "DQ8_A3") (pintype "bidirectional"))
    )
    (net (code "94") (name "/DDR4_DQ57") (class "Default")
      (node (ref "IC4") (pin "B8") (pinfunction "DQ9_B8") (pintype "bidirectional"))
    )
    (net (code "95") (name "/DDR4_DQ58") (class "Default")
      (node (ref "IC4") (pin "C3") (pinfunction "DQ10_C3") (pintype "bidirectional"))
    )
    (net (code "96") (name "/DDR4_DQ59") (class "Default")
      (node (ref "IC4") (pin "C7") (pinfunction "DQ11_C7") (pintype "bidirectional"))
    )
    (net (code "97") (name "/DDR4_DQ60") (class "Default")
      (node (ref "IC4") (pin "C2") (pinfunction "DQ12_C2") (pintype "bidirectional"))
    )
    (net (code "98") (name "/DDR4_DQ61") (class "Default")
      (node (ref "IC4") (pin "C8") (pinfunction "DQ13_C8") (pintype "bidirectional"))
    )
    (net (code "99") (name "/DDR4_DQ62") (class "Default")
      (node (ref "IC4") (pin "D3") (pinfunction "DQ14_D3") (pintype "bidirectional"))
    )
    (net (code "100") (name "/DDR4_DQ63") (class "Default")
      (node (ref "IC4") (pin "D7") (pinfunction "DQ15_D7") (pintype "bidirectional"))
    )
    (net (code "101") (name "/DDR4_DQS0_N") (class "Default")
      (node (ref "IC1") (pin "F3") (pinfunction "LDQS_c_F3") (pintype "bidirectional"))
    )
    (net (code "102") (name "/DDR4_DQS0_P") (class "Default")
      (node (ref "IC1") (pin "G3") (pinfunction "LDQS_t_G3") (pintype "bidirectional"))
    )
    (net (code "103") (name "/DDR4_DQS1_N") (class "Default")
      (node (ref "IC1") (pin "A7") (pinfunction "UDQS_c_A7") (pintype "bidirectional"))
    )
    (net (code "104") (name "/DDR4_DQS1_P") (class "Default")
      (node (ref "IC1") (pin "B7") (pinfunction "UDQS_t_B7") (pintype "bidirectional"))
    )
    (net (code "105") (name "/DDR4_DQS2_N") (class "Default")
      (node (ref "IC2") (pin "F3") (pinfunction "LDQS_c_F3") (pintype "bidirectional"))
    )
    (net (code "106") (name "/DDR4_DQS2_P") (class "Default")
      (node (ref "IC2") (pin "G3") (pinfunction "LDQS_t_G3") (pintype "bidirectional"))
    )
    (net (code "107") (name "/DDR4_DQS3_N") (class "Default")
      (node (ref "IC2") (pin "A7") (pinfunction "UDQS_c_A7") (pintype "bidirectional"))
    )
    (net (code "108") (name "/DDR4_DQS3_P") (class "Default")
      (node (ref "IC2") (pin "B7") (pinfunction "UDQS_t_B7") (pintype "bidirectional"))
    )
    (net (code "109") (name "/DDR4_DQS4_N") (class "Default")
      (node (ref "IC3") (pin "F3") (pinfunction "LDQS_c_F3") (pintype "bidirectional"))
    )
    (net (code "110") (name "/DDR4_DQS4_P") (class "Default")
      (node (ref "IC3") (pin "G3") (pinfunction "LDQS_t_G3") (pintype "bidirectional"))
    )
    (net (code "111") (name "/DDR4_DQS5_N") (class "Default")
      (node (ref "IC3") (pin "A7") (pinfunction "UDQS_c_A7") (pintype "bidirectional"))
    )
    (net (code "112") (name "/DDR4_DQS5_P") (class "Default")
      (node (ref "IC3") (pin "B7") (pinfunction "UDQS_t_B7") (pintype "bidirectional"))
    )
    (net (code "113") (name "/DDR4_DQS6_N") (class "Default")
      (node (ref "IC4") (pin "F3") (pinfunction "LDQS_c_F3") (pintype "bidirectional"))
    )
    (net (code "114") (name "/DDR4_DQS6_P") (class "Default")
      (node (ref "IC4") (pin "G3") (pinfunction "LDQS_t_G3") (pintype "bidirectional"))
    )
    (net (code "115") (name "/DDR4_DQS7_N") (class "Default")
      (node (ref "IC4") (pin "A7") (pinfunction "UDQS_c_A7") (pintype "bidirectional"))
    )
    (net (code "116") (name "/DDR4_DQS7_P") (class "Default")
      (node (ref "IC4") (pin "B7") (pinfunction "UDQS_t_B7") (pintype "bidirectional"))
    )
    (net (code "118") (name "/DDR4_ODT") (class "Default")
      (node (ref "IC1") (pin "K3") (pinfunction "ODT_K3") (pintype "input"))
      (node (ref "IC2") (pin "K3") (pinfunction "ODT_K3") (pintype "input"))
      (node (ref "IC3") (pin "K3") (pinfunction "ODT_K3") (pintype "input"))
      (node (ref "IC4") (pin "K3") (pinfunction "ODT_K3") (pintype "input"))
      (node (ref "R26") (pin "2") (pinfunction "2_2") (pintype "passive"))
    )
    (net (code "119") (name "/DDR4_PAR") (class "Default")
      (node (ref "IC1") (pin "T3") (pinfunction "PAR_T3") (pintype "input"))
      (node (ref "IC2") (pin "T3") (pinfunction "PAR_T3") (pintype "input"))
      (node (ref "IC3") (pin "T3") (pinfunction "PAR_T3") (pintype "input"))
      (node (ref "IC4") (pin "T3") (pinfunction "PAR_T3") (pintype "input"))
      (node (ref "R23") (pin "2") (pinfunction "2_2") (pintype "passive"))
    )
    (net (code "120") (name "/DDR4_RESET_B") (class "Default")
      (node (ref "IC1") (pin "P1") (pinfunction "~{RESET}_P1") (pintype "input"))
      (node (ref "IC2") (pin "P1") (pinfunction "~{RESET}_P1") (pintype "input"))
      (node (ref "IC3") (pin "P1") (pinfunction "~{RESET}_P1") (pintype "input"))
      (node (ref "IC4") (pin "P1") (pinfunction "~{RESET}_P1") (pintype "input"))
      (node (ref "R21") (pin "2") (pinfunction "2_2") (pintype "passive"))
    )
    (net (code "122") (name "/DDR4_TEN") (class "Default")
      (node (ref "IC1") (pin "N9") (pinfunction "TEN_N9") (pintype "input"))
      (node (ref "IC2") (pin "N9") (pinfunction "TEN_N9") (pintype "input"))
      (node (ref "IC3") (pin "N9") (pinfunction "TEN_N9") (pintype "input"))
      (node (ref "IC4") (pin "N9") (pinfunction "TEN_N9") (pintype "input"))
      (node (ref "R25") (pin "2") (pinfunction "2_2") (pintype "passive"))
    )
    (net (code "123") (name "/DDR4_VREFA") (class "Default")
      (node (ref "C2") (pin "1") (pinfunction "1_1") (pintype "passive"))
      (node (ref "IC1") (pin "M1") (pinfunction "VREFCA_M1") (pintype "power_in"))
      (node (ref "R35") (pin "1") (pinfunction "1_1") (pintype "passive"))
      (node (ref "R36") (pin "2") (pinfunction "2_2") (pintype "passive"))
    )
    (net (code "124") (name "/DDR4_VREFB") (class "Default")
      (node (ref "C12") (pin "1") (pinfunction "1_1") (pintype "passive"))
      (node (ref "IC2") (pin "M1") (pinfunction "VREFCA_M1") (pintype "power_in"))
      (node (ref "R38") (pin "1") (pinfunction "1_1") (pintype "passive"))
      (node (ref "R41") (pin "2") (pinfunction "2_2") (pintype "passive"))
    )
    (net (code "125") (name "/DDR4_VREFC") (class "Default")
      (node (ref "C13") (pin "1") (pinfunction "1_1") (pintype "passive"))
      (node (ref "IC3") (pin "M1") (pinfunction "VREFCA_M1") (pintype "power_in"))
      (node (ref "R39") (pin "1") (pinfunction "1_1") (pintype "passive"))
      (node (ref "R42") (pin "2") (pinfunction "2_2") (pintype "passive"))
    )
    (net (code "126") (name "/DDR4_VREFD") (class "Default")
      (node (ref "C14") (pin "1") (pinfunction "1_1") (pintype "passive"))
      (node (ref "IC4") (pin "M1") (pinfunction "VREFCA_M1") (pintype "power_in"))
      (node (ref "R40") (pin "1") (pinfunction "1_1") (pintype "passive"))
      (node (ref "R43") (pin "2") (pinfunction "2_2") (pintype "passive"))
    )
    (net (code "127") (name "/DDR4_ZQA") (class "Default")
      (node (ref "IC1") (pin "F9") (pinfunction "ZQ_F9") (pintype "power_in"))
      (node (ref "R33") (pin "2") (pinfunction "2_2") (pintype "passive"))
    )
    (net (code "128") (name "/DDR4_ZQB") (class "Default")
      (node (ref "IC2") (pin "F9") (pinfunction "ZQ_F9") (pintype "power_in"))
      (node (ref "R34") (pin "2") (pinfunction "2_2") (pintype "passive"))
    )
    (net (code "129") (name "/DDR4_ZQC") (class "Default")
      (node (ref "IC3") (pin "F9") (pinfunction "ZQ_F9") (pintype "power_in"))
      (node (ref "R29") (pin "2") (pinfunction "2_2") (pintype "passive"))
    )
    (net (code "130") (name "/DDR4_ZQD") (class "Default")
      (node (ref "IC4") (pin "F9") (pinfunction "ZQ_F9") (pintype "power_in"))
      (node (ref "R27") (pin "2") (pinfunction "2_2") (pintype "passive"))
    )
    (net (code "131") (name "/PGOOD") (class "Default")
      (node (ref "IC5") (pin "9") (pinfunction "PGOOD_9") (pintype "output"))
    )
    (net (code "132") (name "/REFIN") (class "Default")
      (node (ref "C19") (pin "2") (pinfunction "2_2") (pintype "passive"))
      (node (ref "IC5") (pin "1") (pinfunction "REFIN_1") (pintype "input"))
      (node (ref "R44") (pin "2") (pinfunction "2_2") (pintype "passive"))
      (node (ref "R46") (pin "2") (pinfunction "2_2") (pintype "passive"))
    )
    (net (code "133") (name "/VOSNS") (class "Default")
      (node (ref "C18") (pin "2") (pinfunction "2_2") (pintype "passive"))
      (node (ref "IC5") (pin "5") (pinfunction "VOSNS_5") (pintype "input"))
      (node (ref "R45") (pin "1") (pinfunction "1_1") (pintype "passive"))
    )
    (net (code "134") (name "/VTT64") (class "Default")
      (node (ref "C16") (pin "2") (pinfunction "2_2") (pintype "passive"))
      (node (ref "C17") (pin "2") (pinfunction "2_2") (pintype "passive"))
      (node (ref "C38") (pin "1") (pinfunction "1_1") (pintype "passive"))
      (node (ref "C39") (pin "1") (pinfunction "1_1") (pintype "passive"))
      (node (ref "C40") (pin "1") (pinfunction "1_1") (pintype "passive"))
      (node (ref "C41") (pin "1") (pinfunction "1_1") (pintype "passive"))
      (node (ref "C42") (pin "1") (pinfunction "1_1") (pintype "passive"))
      (node (ref "C58") (pin "1") (pinfunction "1_1") (pintype "passive"))
      (node (ref "C59") (pin "1") (pinfunction "1_1") (pintype "passive"))
      (node (ref "C60") (pin "1") (pinfunction "1_1") (pintype "passive"))
      (node (ref "C61") (pin "1") (pinfunction "1_1") (pintype "passive"))
      (node (ref "C70") (pin "1") (pinfunction "1_1") (pintype "passive"))
      (node (ref "C71") (pin "1") (pinfunction "1_1") (pintype "passive"))
      (node (ref "C72") (pin "1") (pinfunction "1_1") (pintype "passive"))
      (node (ref "C73") (pin "1") (pinfunction "1_1") (pintype "passive"))
      (node (ref "IC5") (pin "3") (pinfunction "VO_3") (pintype "power_in"))
      (node (ref "R1") (pin "1") (pinfunction "1_1") (pintype "passive"))
      (node (ref "R10") (pin "1") (pinfunction "1_1") (pintype "passive"))
      (node (ref "R11") (pin "1") (pinfunction "1_1") (pintype "passive"))
      (node (ref "R12") (pin "1") (pinfunction "1_1") (pintype "passive"))
      (node (ref "R13") (pin "1") (pinfunction "1_1") (pintype "passive"))
      (node (ref "R14") (pin "1") (pinfunction "1_1") (pintype "passive"))
      (node (ref "R15") (pin "1") (pinfunction "1_1") (pintype "passive"))
      (node (ref "R16") (pin "1") (pinfunction "1_1") (pintype "passive"))
      (node (ref "R17") (pin "1") (pinfunction "1_1") (pintype "passive"))
      (node (ref "R2") (pin "1") (pinfunction "1_1") (pintype "passive"))
      (node (ref "R20") (pin "1") (pinfunction "1_1") (pintype "passive"))
      (node (ref "R22") (pin "1") (pinfunction "1_1") (pintype "passive"))
      (node (ref "R23") (pin "1") (pinfunction "1_1") (pintype "passive"))
      (node (ref "R24") (pin "1") (pinfunction "1_1") (pintype "passive"))
      (node (ref "R26") (pin "1") (pinfunction "1_1") (pintype "passive"))
      (node (ref "R28") (pin "1") (pinfunction "1_1") (pintype "passive"))
      (node (ref "R3") (pin "1") (pinfunction "1_1") (pintype "passive"))
      (node (ref "R31") (pin "1") (pinfunction "1_1") (pintype "passive"))
      (node (ref "R32") (pin "1") (pinfunction "1_1") (pintype "passive"))
      (node (ref "R4") (pin "1") (pinfunction "1_1") (pintype "passive"))
      (node (ref "R45") (pin "2") (pinfunction "2_2") (pintype "passive"))
      (node (ref "R5") (pin "1") (pinfunction "1_1") (pintype "passive"))
      (node (ref "R6") (pin "1") (pinfunction "1_1") (pintype "passive"))
      (node (ref "R7") (pin "1") (pinfunction "1_1") (pintype "passive"))
      (node (ref "R8") (pin "1") (pinfunction "1_1") (pintype "passive"))
      (node (ref "R9") (pin "1") (pinfunction "1_1") (pintype "passive"))
    )
    (net (code "136") (name "GND") (class "Default")
      (node (ref "C10") (pin "2") (pinfunction "2_2") (pintype "passive"))
      (node (ref "C11") (pin "2") (pinfunction "2_2") (pintype "passive"))
      (node (ref "C12") (pin "2") (pinfunction "2_2") (pintype "passive"))
      (node (ref "C13") (pin "2") (pinfunction "2_2") (pintype "passive"))
      (node (ref "C14") (pin "2") (pinfunction "2_2") (pintype "passive"))
      (node (ref "C15") (pin "2") (pinfunction "2_2") (pintype "passive"))
      (node (ref "C16") (pin "1") (pinfunction "1_1") (pintype "passive"))
      (node (ref "C17") (pin "1") (pinfunction "1_1") (pintype "passive"))
      (node (ref "C18") (pin "1") (pinfunction "1_1") (pintype "passive"))
      (node (ref "C19") (pin "1") (pinfunction "1_1") (pintype "passive"))
      (node (ref "C2") (pin "2") (pinfunction "2_2") (pintype "passive"))
      (node (ref "C20") (pin "1") (pinfunction "1_1") (pintype "passive"))
      (node (ref "C21") (pin "2") (pinfunction "2_2") (pintype "passive"))
      (node (ref "C22") (pin "2") (pinfunction "2_2") (pintype "passive"))
      (node (ref "C23") (pin "2") (pinfunction "2_2") (pintype "passive"))
      (node (ref "C24") (pin "2") (pinfunction "2_2") (pintype "passive"))
      (node (ref "C25") (pin "2") (pinfunction "2_2") (pintype "passive"))
      (node (ref "C26") (pin "2") (pinfunction "2_2") (pintype "passive"))
      (node (ref "C27") (pin "2") (pinfunction "2_2") (pintype "passive"))
      (node (ref "C28") (pin "2") (pinfunction "2_2") (pintype "passive"))
      (node (ref "C29") (pin "2") (pinfunction "2_2") (pintype "passive"))
      (node (ref "C3") (pin "2") (pinfunction "2_2") (pintype "passive"))
      (node (ref "C30") (pin "2") (pinfunction "2_2") (pintype "passive"))
      (node (ref "C31") (pin "2") (pinfunction "2_2") (pintype "passive"))
      (node (ref "C32") (pin "2") (pinfunction "2_2") (pintype "passive"))
      (node (ref "C33") (pin "2") (pinfunction "2_2") (pintype "passive"))
      (node (ref "C34") (pin "2") (pinfunction "2_2") (pintype "passive"))
      (node (ref "C35") (pin "2") (pinfunction "2_2") (pintype "passive"))
      (node (ref "C36") (pin "2") (pinfunction "2_2") (pintype "passive"))
      (node (ref "C37") (pin "2") (pinfunction "2_2") (pintype "passive"))
      (node (ref "C38") (pin "2") (pinfunction "2_2") (pintype "passive"))
      (node (ref "C39") (pin "2") (pinfunction "2_2") (pintype "passive"))
      (node (ref "C4") (pin "2") (pinfunction "2_2") (pintype "passive"))
      (node (ref "C40") (pin "2") (pinfunction "2_2") (pintype "passive"))
      (node (ref "C41") (pin "2") (pinfunction "2_2") (pintype "passive"))
      (node (ref "C42") (pin "2") (pinfunction "2_2") (pintype "passive"))
      (node (ref "C43") (pin "2") (pinfunction "2_2") (pintype "passive"))
      (node (ref "C44") (pin "2") (pinfunction "2_2") (pintype "passive"))
      (node (ref "C45") (pin "2") (pinfunction "2_2") (pintype "passive"))
      (node (ref "C46") (pin "2") (pinfunction "2_2") (pintype "passive"))
      (node (ref "C47") (pin "2") (pinfunction "2_2") (pintype "passive"))
      (node (ref "C48") (pin "2") (pinfunction "2_2") (pintype "passive"))
      (node (ref "C49") (pin "2") (pinfunction "2_2") (pintype "passive"))
      (node (ref "C5") (pin "2") (pinfunction "2_2") (pintype "passive"))
      (node (ref "C50") (pin "2") (pinfunction "2_2") (pintype "passive"))
      (node (ref "C51") (pin "2") (pinfunction "2_2") (pintype "passive"))
      (node (ref "C52") (pin "2") (pinfunction "2_2") (pintype "passive"))
      (node (ref "C53") (pin "2") (pinfunction "2_2") (pintype "passive"))
      (node (ref "C54") (pin "2") (pinfunction "2_2") (pintype "passive"))
      (node (ref "C55") (pin "2") (pinfunction "2_2") (pintype "passive"))
      (node (ref "C56") (pin "2") (pinfunction "2_2") (pintype "passive"))
      (node (ref "C57") (pin "2") (pinfunction "2_2") (pintype "passive"))
      (node (ref "C58") (pin "2") (pinfunction "2_2") (pintype "passive"))
      (node (ref "C59") (pin "2") (pinfunction "2_2") (pintype "passive"))
      (node (ref "C6") (pin "2") (pinfunction "2_2") (pintype "passive"))
      (node (ref "C60") (pin "2") (pinfunction "2_2") (pintype "passive"))
      (node (ref "C61") (pin "2") (pinfunction "2_2") (pintype "passive"))
      (node (ref "C62") (pin "2") (pinfunction "2_2") (pintype "passive"))
      (node (ref "C63") (pin "2") (pinfunction "2_2") (pintype "passive"))
      (node (ref "C64") (pin "2") (pinfunction "2_2") (pintype "passive"))
      (node (ref "C65") (pin "2") (pinfunction "2_2") (pintype "passive"))
      (node (ref "C66") (pin "2") (pinfunction "2_2") (pintype "passive"))
      (node (ref "C67") (pin "2") (pinfunction "2_2") (pintype "passive"))
      (node (ref "C68") (pin "2") (pinfunction "2_2") (pintype "passive"))
      (node (ref "C69") (pin "2") (pinfunction "2_2") (pintype "passive"))
      (node (ref "C7") (pin "2") (pinfunction "2_2") (pintype "passive"))
      (node (ref "C70") (pin "2") (pinfunction "2_2") (pintype "passive"))
      (node (ref "C71") (pin "2") (pinfunction "2_2") (pintype "passive"))
      (node (ref "C72") (pin "2") (pinfunction "2_2") (pintype "passive"))
      (node (ref "C73") (pin "2") (pinfunction "2_2") (pintype "passive"))
      (node (ref "C74") (pin "2") (pinfunction "2_2") (pintype "passive"))
      (node (ref "C75") (pin "2") (pinfunction "2_2") (pintype "passive"))
      (node (ref "C76") (pin "2") (pinfunction "2_2") (pintype "passive"))
      (node (ref "C77") (pin "1") (pinfunction "1_1") (pintype "passive"))
      (node (ref "C8") (pin "2") (pinfunction "2_2") (pintype "passive"))
      (node (ref "C9") (pin "2") (pinfunction "2_2") (pintype "passive"))
      (node (ref "IC1") (pin "A2") (pinfunction "VSSQ_A2") (pintype "power_in"))
      (node (ref "IC1") (pin "A8") (pinfunction "VSSQ_A8") (pintype "power_in"))
      (node (ref "IC1") (pin "B2") (pinfunction "VSS_B2") (pintype "power_in"))
      (node (ref "IC1") (pin "C9") (pinfunction "VSSQ_C9") (pintype "power_in"))
      (node (ref "IC1") (pin "D2") (pinfunction "VSSQ_D2") (pintype "power_in"))
      (node (ref "IC1") (pin "D8") (pinfunction "VSSQ_D8") (pintype "power_in"))
      (node (ref "IC1") (pin "E1") (pinfunction "VSS_E1") (pintype "power_in"))
      (node (ref "IC1") (pin "E3") (pinfunction "VSSQ_E3") (pintype "power_in"))
      (node (ref "IC1") (pin "E8") (pinfunction "VSSQ_E8") (pintype "power_in"))
      (node (ref "IC1") (pin "E9") (pinfunction "VSS_E9") (pintype "power_in"))
      (node (ref "IC1") (pin "F1") (pinfunction "VSSQ_F1") (pintype "power_in"))
      (node (ref "IC1") (pin "G8") (pinfunction "VSS_G8") (pintype "power_in"))
      (node (ref "IC1") (pin "H1") (pinfunction "VSSQ_H1") (pintype "power_in"))
      (node (ref "IC1") (pin "H9") (pinfunction "VSSQ_H9") (pintype "power_in"))
      (node (ref "IC1") (pin "K1") (pinfunction "VSS_K1") (pintype "power_in"))
      (node (ref "IC1") (pin "K9") (pinfunction "VSS_K9") (pintype "power_in"))
      (node (ref "IC1") (pin "M9") (pinfunction "VSS_M9") (pintype "power_in"))
      (node (ref "IC1") (pin "N1") (pinfunction "VSS_N1") (pintype "power_in"))
      (node (ref "IC1") (pin "T1") (pinfunction "VSS_T1") (pintype "power_in"))
      (node (ref "IC2") (pin "A2") (pinfunction "VSSQ_A2") (pintype "power_in"))
      (node (ref "IC2") (pin "A8") (pinfunction "VSSQ_A8") (pintype "power_in"))
      (node (ref "IC2") (pin "B2") (pinfunction "VSS_B2") (pintype "power_in"))
      (node (ref "IC2") (pin "C9") (pinfunction "VSSQ_C9") (pintype "power_in"))
      (node (ref "IC2") (pin "D2") (pinfunction "VSSQ_D2") (pintype "power_in"))
      (node (ref "IC2") (pin "D8") (pinfunction "VSSQ_D8") (pintype "power_in"))
      (node (ref "IC2") (pin "E1") (pinfunction "VSS_E1") (pintype "power_in"))
      (node (ref "IC2") (pin "E3") (pinfunction "VSSQ_E3") (pintype "power_in"))
      (node (ref "IC2") (pin "E8") (pinfunction "VSSQ_E8") (pintype "power_in"))
      (node (ref "IC2") (pin "E9") (pinfunction "VSS_E9") (pintype "power_in"))
      (node (ref "IC2") (pin "F1") (pinfunction "VSSQ_F1") (pintype "power_in"))
      (node (ref "IC2") (pin "G8") (pinfunction "VSS_G8") (pintype "power_in"))
      (node (ref "IC2") (pin "H1") (pinfunction "VSSQ_H1") (pintype "power_in"))
      (node (ref "IC2") (pin "H9") (pinfunction "VSSQ_H9") (pintype "power_in"))
      (node (ref "IC2") (pin "K1") (pinfunction "VSS_K1") (pintype "power_in"))
      (node (ref "IC2") (pin "K9") (pinfunction "VSS_K9") (pintype "power_in"))
      (node (ref "IC2") (pin "M9") (pinfunction "VSS_M9") (pintype "power_in"))
      (node (ref "IC2") (pin "N1") (pinfunction "VSS_N1") (pintype "power_in"))
      (node (ref "IC2") (pin "T1") (pinfunction "VSS_T1") (pintype "power_in"))
      (node (ref "IC3") (pin "A2") (pinfunction "VSSQ_A2") (pintype "power_in"))
      (node (ref "IC3") (pin "A8") (pinfunction "VSSQ_A8") (pintype "power_in"))
      (node (ref "IC3") (pin "B2") (pinfunction "VSS_B2") (pintype "power_in"))
      (node (ref "IC3") (pin "C9") (pinfunction "VSSQ_C9") (pintype "power_in"))
      (node (ref "IC3") (pin "D2") (pinfunction "VSSQ_D2") (pintype "power_in"))
      (node (ref "IC3") (pin "D8") (pinfunction "VSSQ_D8") (pintype "power_in"))
      (node (ref "IC3") (pin "E1") (pinfunction "VSS_E1") (pintype "power_in"))
      (node (ref "IC3") (pin "E3") (pinfunction "VSSQ_E3") (pintype "power_in"))
      (node (ref "IC3") (pin "E8") (pinfunction "VSSQ_E8") (pintype "power_in"))
      (node (ref "IC3") (pin "E9") (pinfunction "VSS_E9") (pintype "power_in"))
      (node (ref "IC3") (pin "F1") (pinfunction "VSSQ_F1") (pintype "power_in"))
      (node (ref "IC3") (pin "G8") (pinfunction "VSS_G8") (pintype "power_in"))
      (node (ref "IC3") (pin "H1") (pinfunction "VSSQ_H1") (pintype "power_in"))
      (node (ref "IC3") (pin "H9") (pinfunction "VSSQ_H9") (pintype "power_in"))
      (node (ref "IC3") (pin "K1") (pinfunction "VSS_K1") (pintype "power_in"))
      (node (ref "IC3") (pin "K9") (pinfunction "VSS_K9") (pintype "power_in"))
      (node (ref "IC3") (pin "M9") (pinfunction "VSS_M9") (pintype "power_in"))
      (node (ref "IC3") (pin "N1") (pinfunction "VSS_N1") (pintype "power_in"))
      (node (ref "IC3") (pin "T1") (pinfunction "VSS_T1") (pintype "power_in"))
      (node (ref "IC4") (pin "A2") (pinfunction "VSSQ_A2") (pintype "power_in"))
      (node (ref "IC4") (pin "A8") (pinfunction "VSSQ_A8") (pintype "power_in"))
      (node (ref "IC4") (pin "B2") (pinfunction "VSS_B2") (pintype "power_in"))
      (node (ref "IC4") (pin "C9") (pinfunction "VSSQ_C9") (pintype "power_in"))
      (node (ref "IC4") (pin "D2") (pinfunction "VSSQ_D2") (pintype "power_in"))
      (node (ref "IC4") (pin "D8") (pinfunction "VSSQ_D8") (pintype "power_in"))
      (node (ref "IC4") (pin "E1") (pinfunction "VSS_E1") (pintype "power_in"))
      (node (ref "IC4") (pin "E3") (pinfunction "VSSQ_E3") (pintype "power_in"))
      (node (ref "IC4") (pin "E8") (pinfunction "VSSQ_E8") (pintype "power_in"))
      (node (ref "IC4") (pin "E9") (pinfunction "VSS_E9") (pintype "power_in"))
      (node (ref "IC4") (pin "F1") (pinfunction "VSSQ_F1") (pintype "power_in"))
      (node (ref "IC4") (pin "G8") (pinfunction "VSS_G8") (pintype "power_in"))
      (node (ref "IC4") (pin "H1") (pinfunction "VSSQ_H1") (pintype "power_in"))
      (node (ref "IC4") (pin "H9") (pinfunction "VSSQ_H9") (pintype "power_in"))
      (node (ref "IC4") (pin "K1") (pinfunction "VSS_K1") (pintype "power_in"))
      (node (ref "IC4") (pin "K9") (pinfunction "VSS_K9") (pintype "power_in"))
      (node (ref "IC4") (pin "M9") (pinfunction "VSS_M9") (pintype "power_in"))
      (node (ref "IC4") (pin "N1") (pinfunction "VSS_N1") (pintype "power_in"))
      (node (ref "IC4") (pin "T1") (pinfunction "VSS_T1") (pintype "power_in"))
      (node (ref "IC5") (pin "11") (pinfunction "EP_11") (pintype "power_in"))
      (node (ref "IC5") (pin "4") (pinfunction "PGND_4") (pintype "power_in"))
      (node (ref "IC5") (pin "8") (pinfunction "GND_8") (pintype "power_in"))
      (node (ref "R21") (pin "1") (pinfunction "1_1") (pintype "passive"))
      (node (ref "R25") (pin "1") (pinfunction "1_1") (pintype "passive"))
      (node (ref "R27") (pin "1") (pinfunction "1_1") (pintype "passive"))
      (node (ref "R29") (pin "1") (pinfunction "1_1") (pintype "passive"))
      (node (ref "R33") (pin "1") (pinfunction "1_1") (pintype "passive"))
      (node (ref "R34") (pin "1") (pinfunction "1_1") (pintype "passive"))
      (node (ref "R36") (pin "1") (pinfunction "1_1") (pintype "passive"))
      (node (ref "R41") (pin "1") (pinfunction "1_1") (pintype "passive"))
      (node (ref "R42") (pin "1") (pinfunction "1_1") (pintype "passive"))
      (node (ref "R43") (pin "1") (pinfunction "1_1") (pintype "passive"))
      (node (ref "R46") (pin "1") (pinfunction "1_1") (pintype "passive"))
    )
    (net (code "137") (name "Net-(C1-Pad2)") (class "Default")
      (node (ref "C1") (pin "2") (pinfunction "2_2") (pintype "passive"))
      (node (ref "R18") (pin "1") (pinfunction "1_1") (pintype "passive"))
      (node (ref "R19") (pin "1") (pinfunction "1_1") (pintype "passive"))
    )
    (net (code "138") (name "Net-(IC5-REFOUT)") (class "Default")
      (node (ref "C20") (pin "2") (pinfunction "2_2") (pintype "passive"))
      (node (ref "IC5") (pin "6") (pinfunction "REFOUT_6") (pintype "output"))
    )
    (net (code "139") (name "P1V2") (class "Default")
      (node (ref "C1") (pin "1") (pinfunction "1_1") (pintype "passive"))
      (node (ref "C15") (pin "1") (pinfunction "1_1") (pintype "passive"))
      (node (ref "C23") (pin "1") (pinfunction "1_1") (pintype "passive"))
      (node (ref "C24") (pin "1") (pinfunction "1_1") (pintype "passive"))
      (node (ref "C25") (pin "1") (pinfunction "1_1") (pintype "passive"))
      (node (ref "C26") (pin "1") (pinfunction "1_1") (pintype "passive"))
      (node (ref "C27") (pin "1") (pinfunction "1_1") (pintype "passive"))
      (node (ref "C28") (pin "1") (pinfunction "1_1") (pintype "passive"))
      (node (ref "C29") (pin "1") (pinfunction "1_1") (pintype "passive"))
      (node (ref "C30") (pin "1") (pinfunction "1_1") (pintype "passive"))
      (node (ref "C31") (pin "1") (pinfunction "1_1") (pintype "passive"))
      (node (ref "C32") (pin "1") (pinfunction "1_1") (pintype "passive"))
      (node (ref "C33") (pin "1") (pinfunction "1_1") (pintype "passive"))
      (node (ref "C34") (pin "1") (pinfunction "1_1") (pintype "passive"))
      (node (ref "C35") (pin "1") (pinfunction "1_1") (pintype "passive"))
      (node (ref "C36") (pin "1") (pinfunction "1_1") (pintype "passive"))
      (node (ref "C37") (pin "1") (pinfunction "1_1") (pintype "passive"))
      (node (ref "C43") (pin "1") (pinfunction "1_1") (pintype "passive"))
      (node (ref "C44") (pin "1") (pinfunction "1_1") (pintype "passive"))
      (node (ref "C45") (pin "1") (pinfunction "1_1") (pintype "passive"))
      (node (ref "C46") (pin "1") (pinfunction "1_1") (pintype "passive"))
      (node (ref "C47") (pin "1") (pinfunction "1_1") (pintype "passive"))
      (node (ref "C48") (pin "1") (pinfunction "1_1") (pintype "passive"))
      (node (ref "C49") (pin "1") (pinfunction "1_1") (pintype "passive"))
      (node (ref "C50") (pin "1") (pinfunction "1_1") (pintype "passive"))
      (node (ref "C51") (pin "1") (pinfunction "1_1") (pintype "passive"))
      (node (ref "C52") (pin "1") (pinfunction "1_1") (pintype "passive"))
      (node (ref "C53") (pin "1") (pinfunction "1_1") (pintype "passive"))
      (node (ref "C54") (pin "1") (pinfunction "1_1") (pintype "passive"))
      (node (ref "C55") (pin "1") (pinfunction "1_1") (pintype "passive"))
      (node (ref "C56") (pin "1") (pinfunction "1_1") (pintype "passive"))
      (node (ref "C57") (pin "1") (pinfunction "1_1") (pintype "passive"))
      (node (ref "C62") (pin "1") (pinfunction "1_1") (pintype "passive"))
      (node (ref "C63") (pin "1") (pinfunction "1_1") (pintype "passive"))
      (node (ref "C64") (pin "1") (pinfunction "1_1") (pintype "passive"))
      (node (ref "C65") (pin "1") (pinfunction "1_1") (pintype "passive"))
      (node (ref "C66") (pin "1") (pinfunction "1_1") (pintype "passive"))
      (node (ref "C67") (pin "1") (pinfunction "1_1") (pintype "passive"))
      (node (ref "C68") (pin "1") (pinfunction "1_1") (pintype "passive"))
      (node (ref "C69") (pin "1") (pinfunction "1_1") (pintype "passive"))
      (node (ref "C74") (pin "1") (pinfunction "1_1") (pintype "passive"))
      (node (ref "C75") (pin "1") (pinfunction "1_1") (pintype "passive"))
      (node (ref "C76") (pin "1") (pinfunction "1_1") (pintype "passive"))
      (node (ref "C77") (pin "2") (pinfunction "2_2") (pintype "passive"))
      (node (ref "IC1") (pin "A1") (pinfunction "VDDQ_A1") (pintype "power_in"))
      (node (ref "IC1") (pin "A9") (pinfunction "VDDQ_A9") (pintype "power_in"))
      (node (ref "IC1") (pin "B3") (pinfunction "VDD_B3") (pintype "power_in"))
      (node (ref "IC1") (pin "B9") (pinfunction "VDD_B9") (pintype "power_in"))
      (node (ref "IC1") (pin "C1") (pinfunction "VDDQ_C1") (pintype "power_in"))
      (node (ref "IC1") (pin "D1") (pinfunction "VDD_D1") (pintype "power_in"))
      (node (ref "IC1") (pin "D9") (pinfunction "VDDQ_D9") (pintype "power_in"))
      (node (ref "IC1") (pin "F2") (pinfunction "VDDQ_F2") (pintype "power_in"))
      (node (ref "IC1") (pin "F8") (pinfunction "VDDQ_F8") (pintype "power_in"))
      (node (ref "IC1") (pin "G1") (pinfunction "VDDQ_G1") (pintype "power_in"))
      (node (ref "IC1") (pin "G7") (pinfunction "VDD_G7") (pintype "power_in"))
      (node (ref "IC1") (pin "G9") (pinfunction "VDDQ_G9") (pintype "power_in"))
      (node (ref "IC1") (pin "J1") (pinfunction "VDD_J1") (pintype "power_in"))
      (node (ref "IC1") (pin "J2") (pinfunction "VDDQ_J2") (pintype "power_in"))
      (node (ref "IC1") (pin "J8") (pinfunction "VDDQ_J8") (pintype "power_in"))
      (node (ref "IC1") (pin "J9") (pinfunction "VDD_J9") (pintype "power_in"))
      (node (ref "IC1") (pin "L1") (pinfunction "VDD_L1") (pintype "power_in"))
      (node (ref "IC1") (pin "L9") (pinfunction "VDD_L9") (pintype "power_in"))
      (node (ref "IC1") (pin "R1") (pinfunction "VDD_R1") (pintype "power_in"))
      (node (ref "IC1") (pin "T9") (pinfunction "VDD_T9") (pintype "power_in"))
      (node (ref "IC2") (pin "A1") (pinfunction "VDDQ_A1") (pintype "power_in"))
      (node (ref "IC2") (pin "A9") (pinfunction "VDDQ_A9") (pintype "power_in"))
      (node (ref "IC2") (pin "B3") (pinfunction "VDD_B3") (pintype "power_in"))
      (node (ref "IC2") (pin "B9") (pinfunction "VDD_B9") (pintype "power_in"))
      (node (ref "IC2") (pin "C1") (pinfunction "VDDQ_C1") (pintype "power_in"))
      (node (ref "IC2") (pin "D1") (pinfunction "VDD_D1") (pintype "power_in"))
      (node (ref "IC2") (pin "D9") (pinfunction "VDDQ_D9") (pintype "power_in"))
      (node (ref "IC2") (pin "F2") (pinfunction "VDDQ_F2") (pintype "power_in"))
      (node (ref "IC2") (pin "F8") (pinfunction "VDDQ_F8") (pintype "power_in"))
      (node (ref "IC2") (pin "G1") (pinfunction "VDDQ_G1") (pintype "power_in"))
      (node (ref "IC2") (pin "G7") (pinfunction "VDD_G7") (pintype "power_in"))
      (node (ref "IC2") (pin "G9") (pinfunction "VDDQ_G9") (pintype "power_in"))
      (node (ref "IC2") (pin "J1") (pinfunction "VDD_J1") (pintype "power_in"))
      (node (ref "IC2") (pin "J2") (pinfunction "VDDQ_J2") (pintype "power_in"))
      (node (ref "IC2") (pin "J8") (pinfunction "VDDQ_J8") (pintype "power_in"))
      (node (ref "IC2") (pin "J9") (pinfunction "VDD_J9") (pintype "power_in"))
      (node (ref "IC2") (pin "L1") (pinfunction "VDD_L1") (pintype "power_in"))
      (node (ref "IC2") (pin "L9") (pinfunction "VDD_L9") (pintype "power_in"))
      (node (ref "IC2") (pin "R1") (pinfunction "VDD_R1") (pintype "power_in"))
      (node (ref "IC2") (pin "T9") (pinfunction "VDD_T9") (pintype "power_in"))
      (node (ref "IC3") (pin "A1") (pinfunction "VDDQ_A1") (pintype "power_in"))
      (node (ref "IC3") (pin "A9") (pinfunction "VDDQ_A9") (pintype "power_in"))
      (node (ref "IC3") (pin "B3") (pinfunction "VDD_B3") (pintype "power_in"))
      (node (ref "IC3") (pin "B9") (pinfunction "VDD_B9") (pintype "power_in"))
      (node (ref "IC3") (pin "C1") (pinfunction "VDDQ_C1") (pintype "power_in"))
      (node (ref "IC3") (pin "D1") (pinfunction "VDD_D1") (pintype "power_in"))
      (node (ref "IC3") (pin "D9") (pinfunction "VDDQ_D9") (pintype "power_in"))
      (node (ref "IC3") (pin "F2") (pinfunction "VDDQ_F2") (pintype "power_in"))
      (node (ref "IC3") (pin "F8") (pinfunction "VDDQ_F8") (pintype "power_in"))
      (node (ref "IC3") (pin "G1") (pinfunction "VDDQ_G1") (pintype "power_in"))
      (node (ref "IC3") (pin "G7") (pinfunction "VDD_G7") (pintype "power_in"))
      (node (ref "IC3") (pin "G9") (pinfunction "VDDQ_G9") (pintype "power_in"))
      (node (ref "IC3") (pin "J1") (pinfunction "VDD_J1") (pintype "power_in"))
      (node (ref "IC3") (pin "J2") (pinfunction "VDDQ_J2") (pintype "power_in"))
      (node (ref "IC3") (pin "J8") (pinfunction "VDDQ_J8") (pintype "power_in"))
      (node (ref "IC3") (pin "J9") (pinfunction "VDD_J9") (pintype "power_in"))
      (node (ref "IC3") (pin "L1") (pinfunction "VDD_L1") (pintype "power_in"))
      (node (ref "IC3") (pin "L9") (pinfunction "VDD_L9") (pintype "power_in"))
      (node (ref "IC3") (pin "R1") (pinfunction "VDD_R1") (pintype "power_in"))
      (node (ref "IC3") (pin "T9") (pinfunction "VDD_T9") (pintype "power_in"))
      (node (ref "IC4") (pin "A1") (pinfunction "VDDQ_A1") (pintype "power_in"))
      (node (ref "IC4") (pin "A9") (pinfunction "VDDQ_A9") (pintype "power_in"))
      (node (ref "IC4") (pin "B3") (pinfunction "VDD_B3") (pintype "power_in"))
      (node (ref "IC4") (pin "B9") (pinfunction "VDD_B9") (pintype "power_in"))
      (node (ref "IC4") (pin "C1") (pinfunction "VDDQ_C1") (pintype "power_in"))
      (node (ref "IC4") (pin "D1") (pinfunction "VDD_D1") (pintype "power_in"))
      (node (ref "IC4") (pin "D9") (pinfunction "VDDQ_D9") (pintype "power_in"))
      (node (ref "IC4") (pin "F2") (pinfunction "VDDQ_F2") (pintype "power_in"))
      (node (ref "IC4") (pin "F8") (pinfunction "VDDQ_F8") (pintype "power_in"))
      (node (ref "IC4") (pin "G1") (pinfunction "VDDQ_G1") (pintype "power_in"))
      (node (ref "IC4") (pin "G7") (pinfunction "VDD_G7") (pintype "power_in"))
      (node (ref "IC4") (pin "G9") (pinfunction "VDDQ_G9") (pintype "power_in"))
      (node (ref "IC4") (pin "J1") (pinfunction "VDD_J1") (pintype "power_in"))
      (node (ref "IC4") (pin "J2") (pinfunction "VDDQ_J2") (pintype "power_in"))
      (node (ref "IC4") (pin "J8") (pinfunction "VDDQ_J8") (pintype "power_in"))
      (node (ref "IC4") (pin "J9") (pinfunction "VDD_J9") (pintype "power_in"))
      (node (ref "IC4") (pin "L1") (pinfunction "VDD_L1") (pintype "power_in"))
      (node (ref "IC4") (pin "L9") (pinfunction "VDD_L9") (pintype "power_in"))
      (node (ref "IC4") (pin "R1") (pinfunction "VDD_R1") (pintype "power_in"))
      (node (ref "IC4") (pin "T9") (pinfunction "VDD_T9") (pintype "power_in"))
      (node (ref "IC5") (pin "2") (pinfunction "VLDOIN_2") (pintype "input"))
      (node (ref "R30") (pin "1") (pinfunction "1_1") (pintype "passive"))
      (node (ref "R35") (pin "2") (pinfunction "2_2") (pintype "passive"))
      (node (ref "R38") (pin "2") (pinfunction "2_2") (pintype "passive"))
      (node (ref "R39") (pin "2") (pinfunction "2_2") (pintype "passive"))
      (node (ref "R40") (pin "2") (pinfunction "2_2") (pintype "passive"))
      (node (ref "R44") (pin "1") (pinfunction "1_1") (pintype "passive"))
    )
    (net (code "140") (name "P2V5") (class "Default")
      (node (ref "C10") (pin "1") (pinfunction "1_1") (pintype "passive"))
      (node (ref "C11") (pin "1") (pinfunction "1_1") (pintype "passive"))
      (node (ref "C21") (pin "1") (pinfunction "1_1") (pintype "passive"))
      (node (ref "C22") (pin "1") (pinfunction "1_1") (pintype "passive"))
      (node (ref "C3") (pin "1") (pinfunction "1_1") (pintype "passive"))
      (node (ref "C4") (pin "1") (pinfunction "1_1") (pintype "passive"))
      (node (ref "C6") (pin "1") (pinfunction "1_1") (pintype "passive"))
      (node (ref "C7") (pin "1") (pinfunction "1_1") (pintype "passive"))
      (node (ref "C8") (pin "1") (pinfunction "1_1") (pintype "passive"))
      (node (ref "C9") (pin "1") (pinfunction "1_1") (pintype "passive"))
      (node (ref "IC1") (pin "B1") (pinfunction "VPP_B1") (pintype "power_in"))
      (node (ref "IC1") (pin "R9") (pinfunction "VPP_R9") (pintype "power_in"))
      (node (ref "IC2") (pin "B1") (pinfunction "VPP_B1") (pintype "power_in"))
      (node (ref "IC2") (pin "R9") (pinfunction "VPP_R9") (pintype "power_in"))
      (node (ref "IC3") (pin "B1") (pinfunction "VPP_B1") (pintype "power_in"))
      (node (ref "IC3") (pin "R9") (pinfunction "VPP_R9") (pintype "power_in"))
      (node (ref "IC4") (pin "B1") (pinfunction "VPP_B1") (pintype "power_in"))
      (node (ref "IC4") (pin "R9") (pinfunction "VPP_R9") (pintype "power_in"))
    )
    (net (code "141") (name "P3V3") (class "Default")
      (node (ref "C5") (pin "1") (pinfunction "1_1") (pintype "passive"))
      (node (ref "IC5") (pin "10") (pinfunction "VIN_10") (pintype "input"))
      (node (ref "IC5") (pin "7") (pinfunction "EN_7") (pintype "input"))
    )
    (net (code "142") (name "unconnected-(IC1-NC-PadT7)") (class "Default")
      (node (ref "IC1") (pin "T7") (pinfunction "NC_T7") (pintype "power_in"))
    )
    (net (code "143") (name "unconnected-(IC2-NC-PadT7)") (class "Default")
      (node (ref "IC2") (pin "T7") (pinfunction "NC_T7") (pintype "power_in"))
    )
    (net (code "144") (name "unconnected-(IC3-NC-PadT7)") (class "Default")
      (node (ref "IC3") (pin "T7") (pinfunction "NC_T7") (pintype "power_in"))
    )
    (net (code "145") (name "unconnected-(IC4-NC-PadT7)") (class "Default")
      (node (ref "IC4") (pin "T7") (pinfunction "NC_T7") (pintype "power_in"))
    )
  )
)
